# axiom_beta_sensor_cmv12000_tht_v0_16_c4f.net
KiCad netlist of a schematic drawn in EAGLE
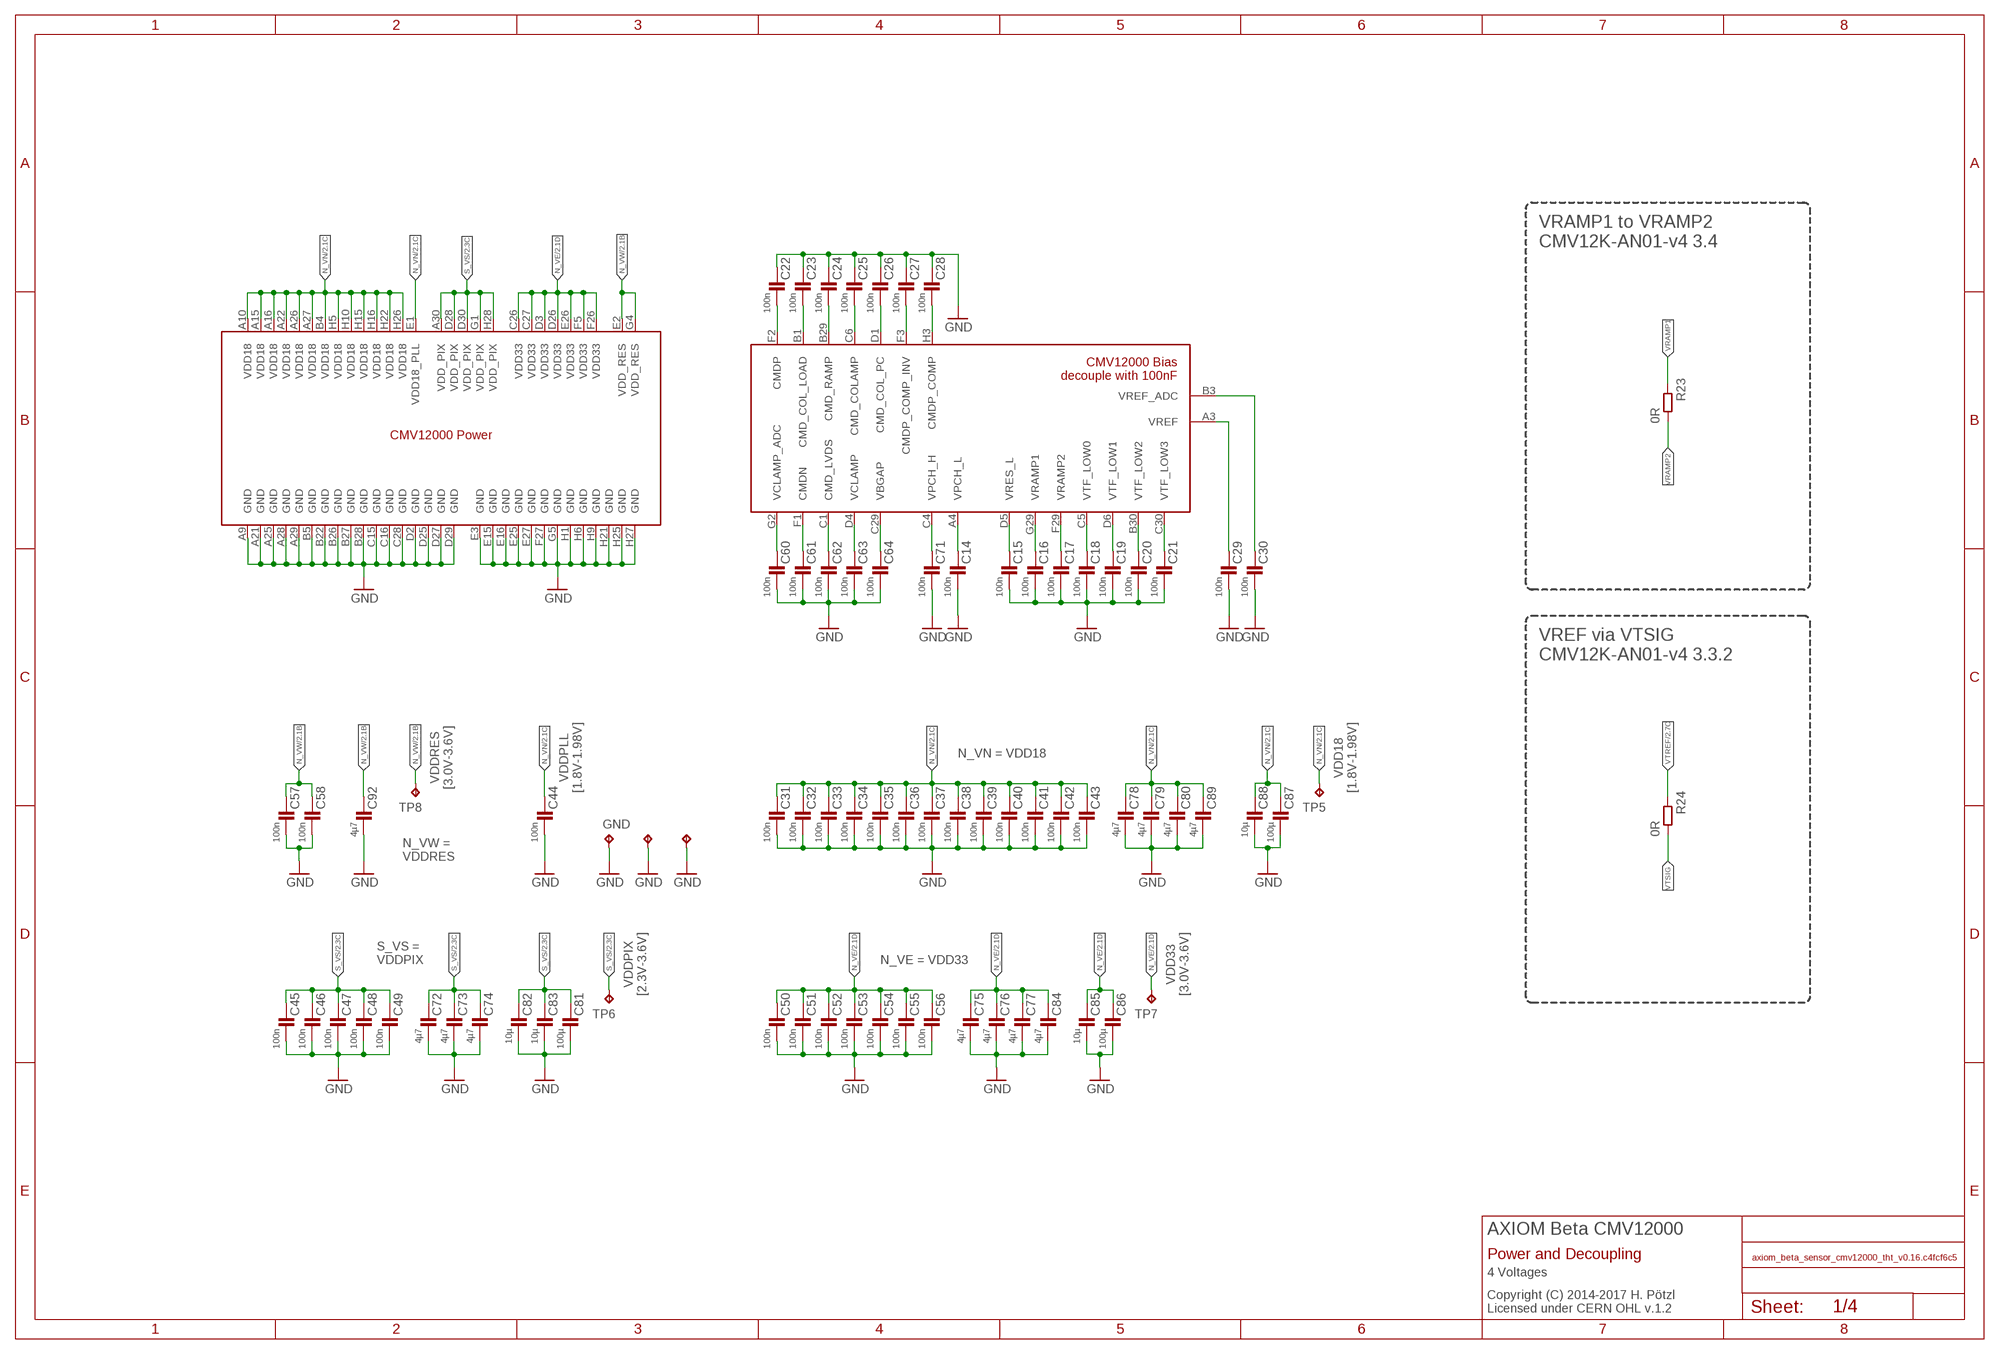
[diagram p0: schematic, sheet 1]
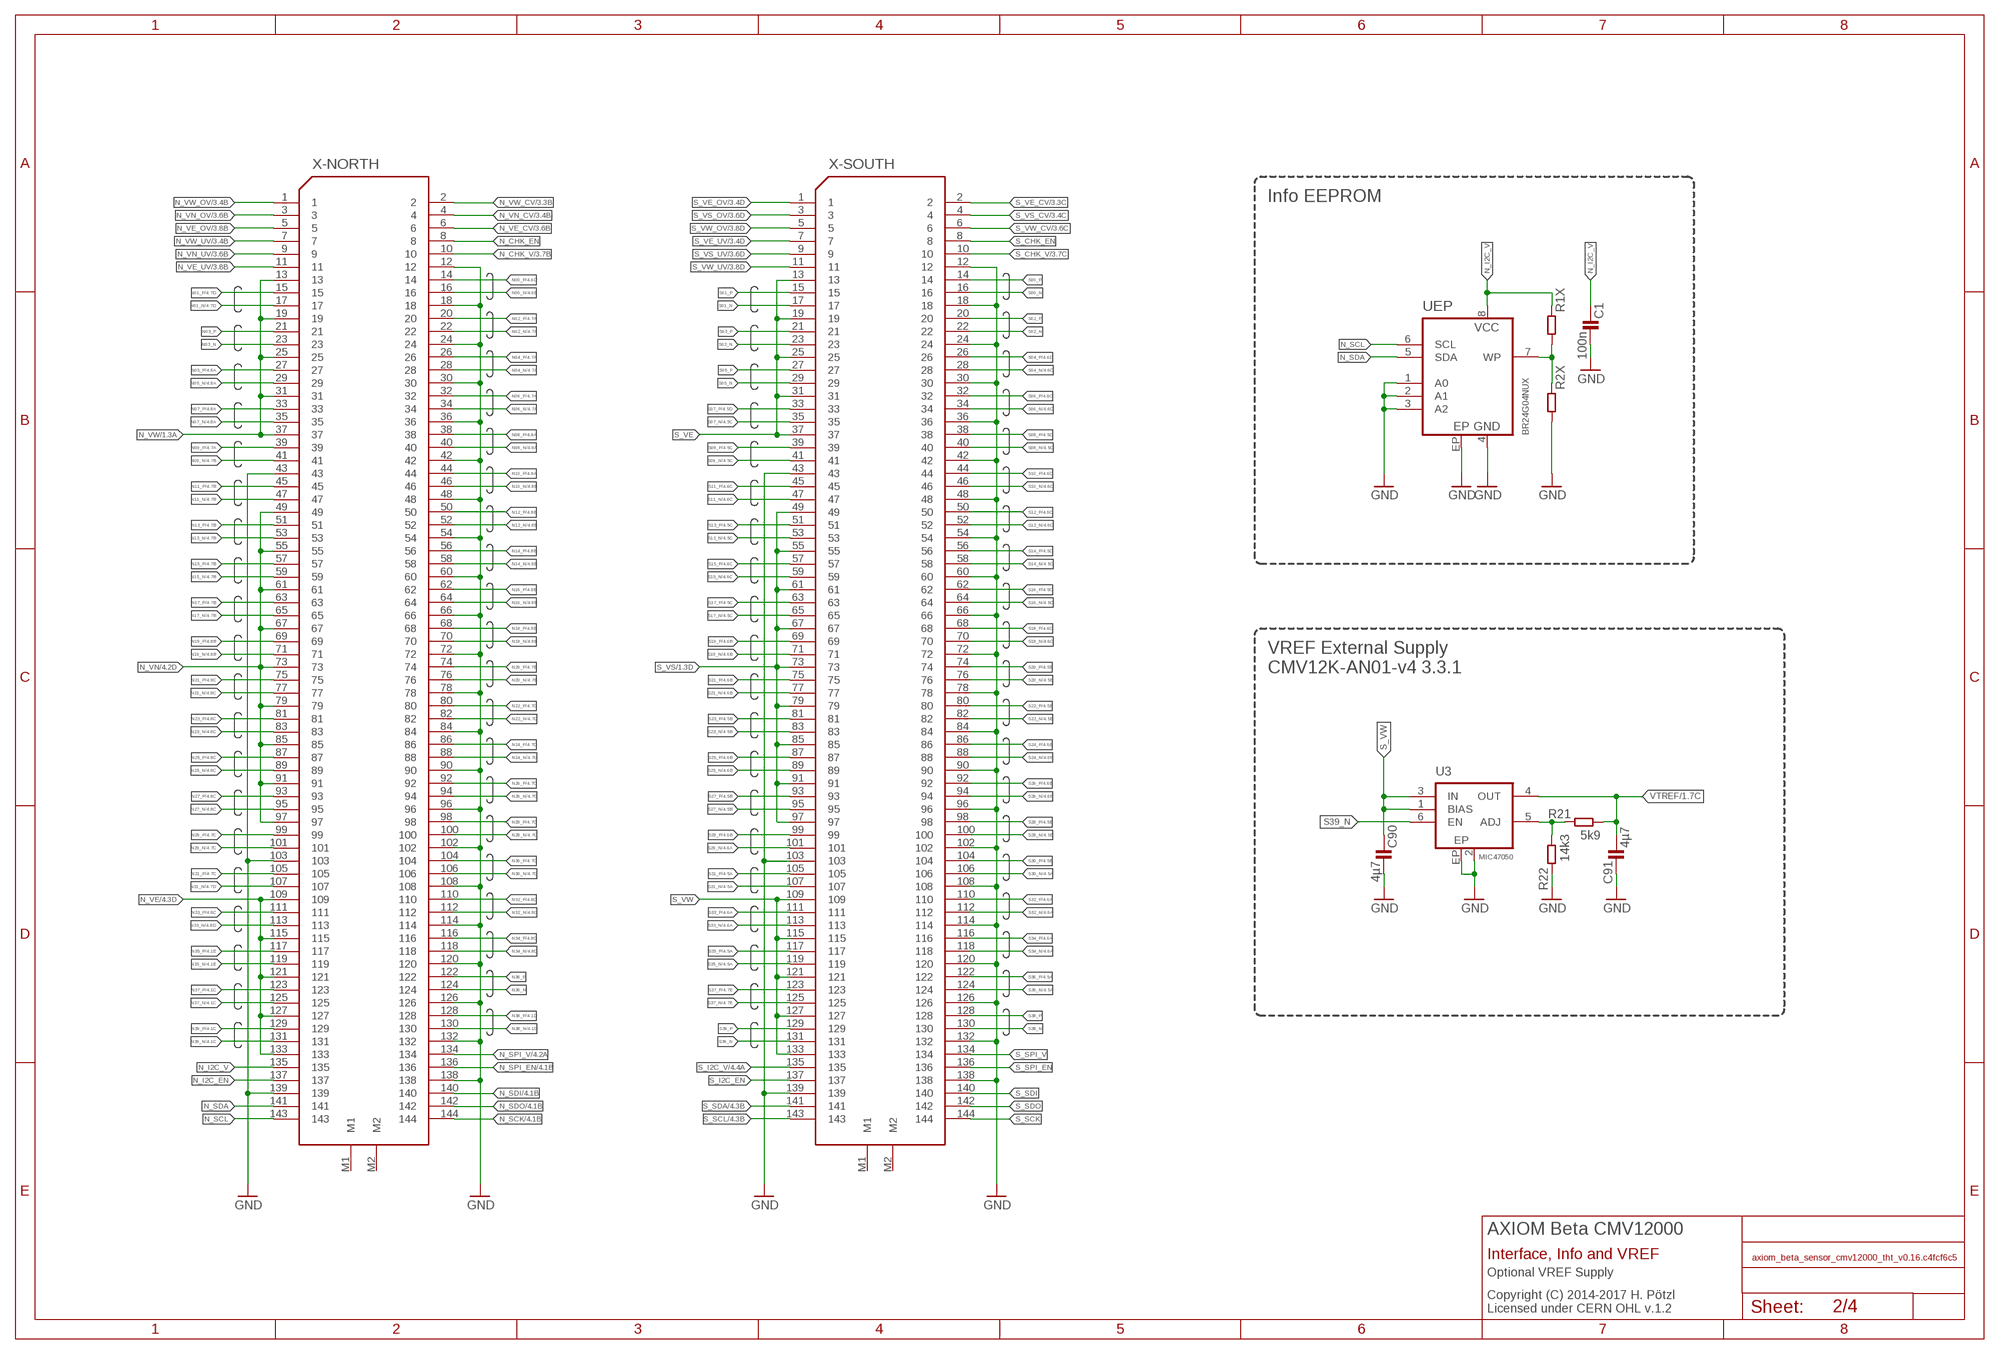
[diagram p1: schematic, sheet 2]
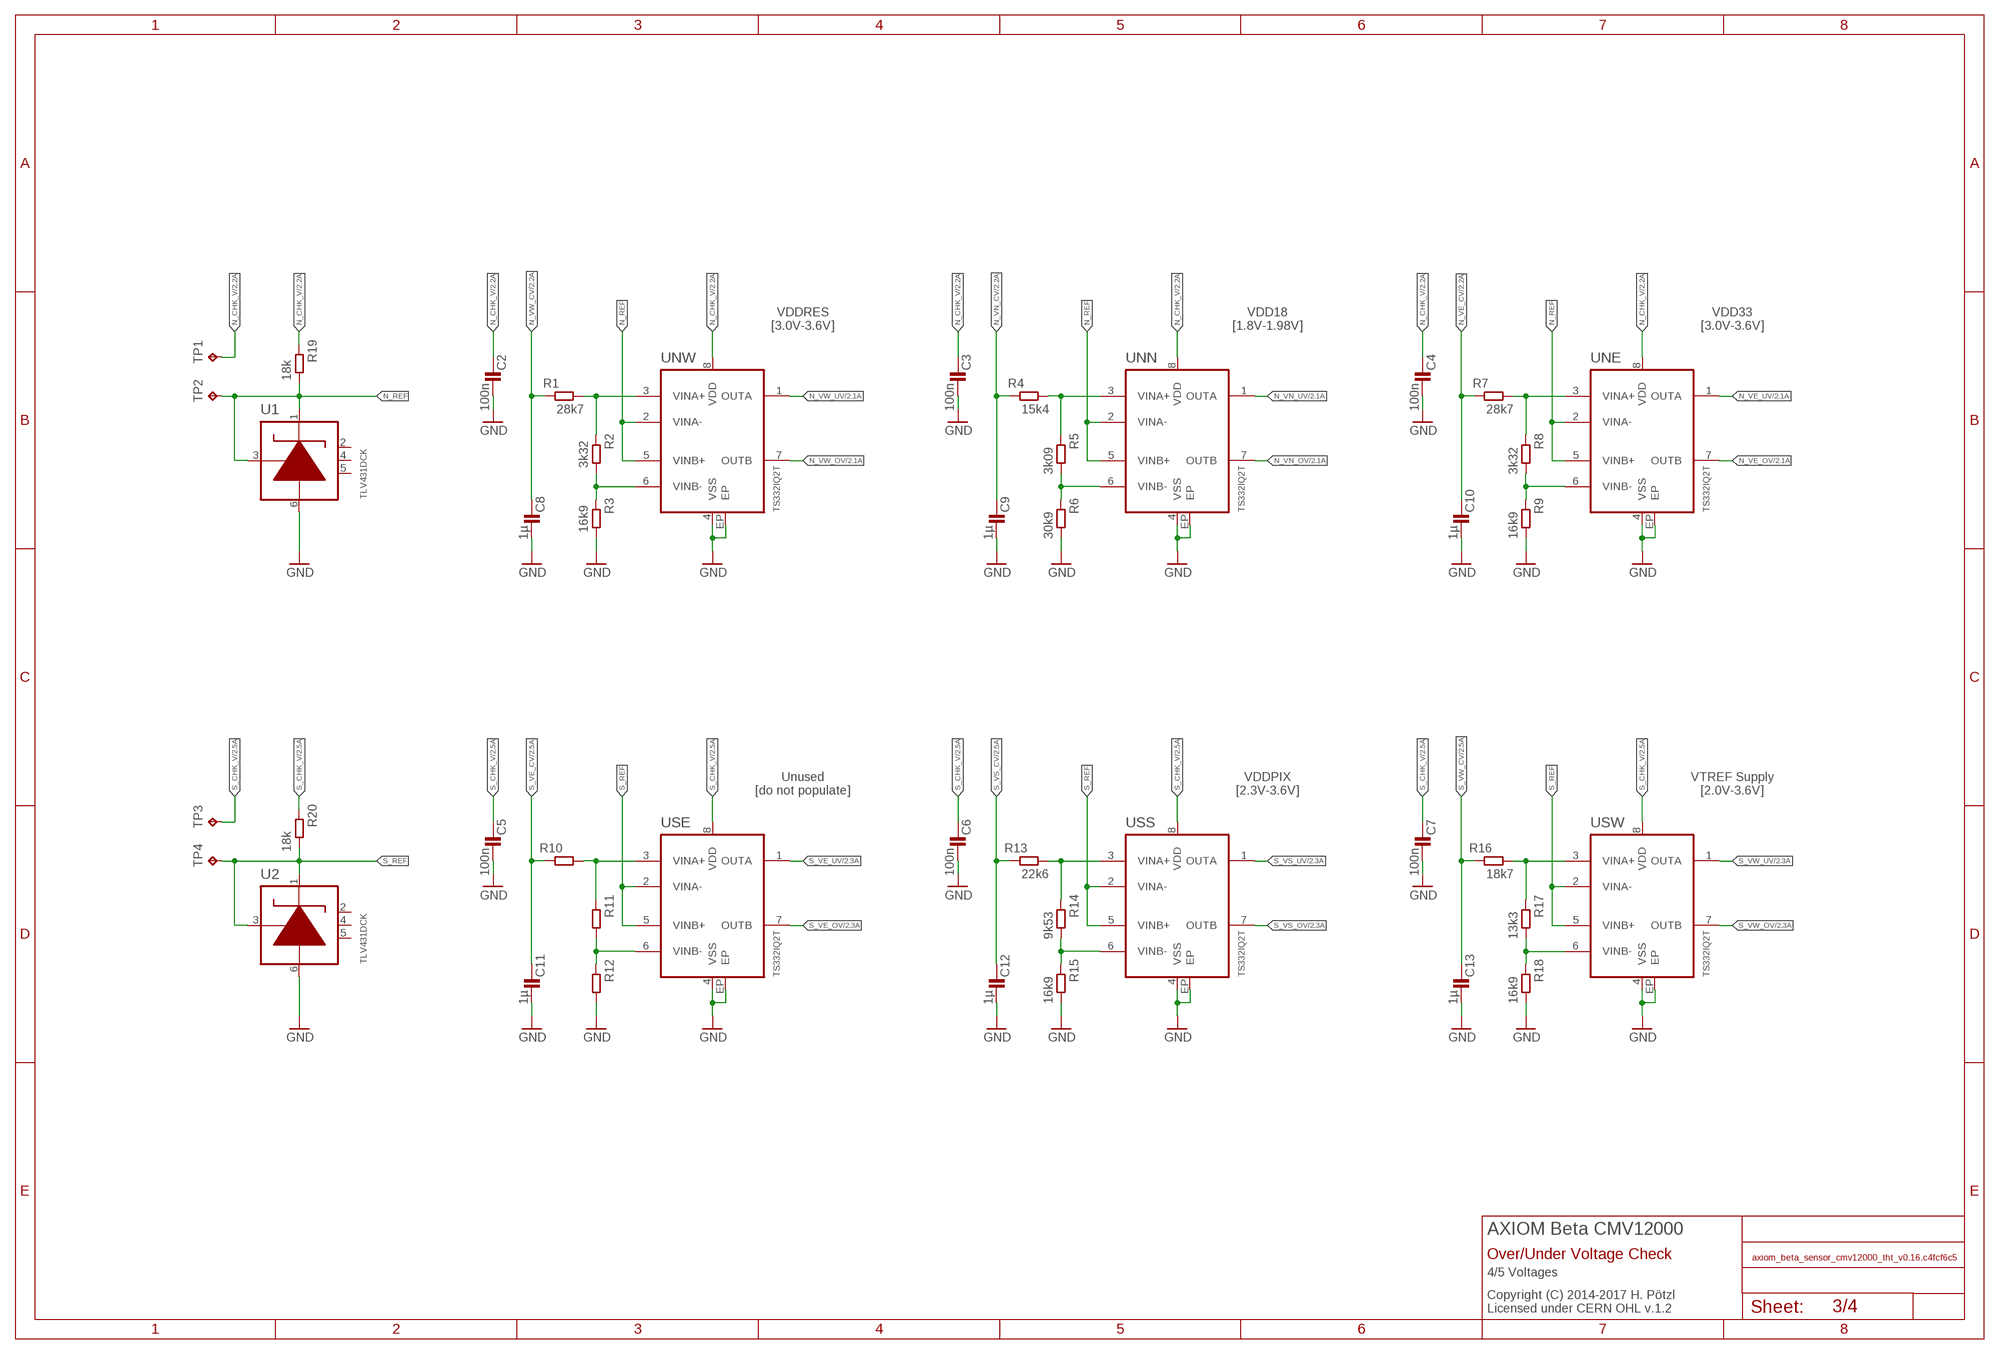
[diagram p2: schematic, sheet 3]
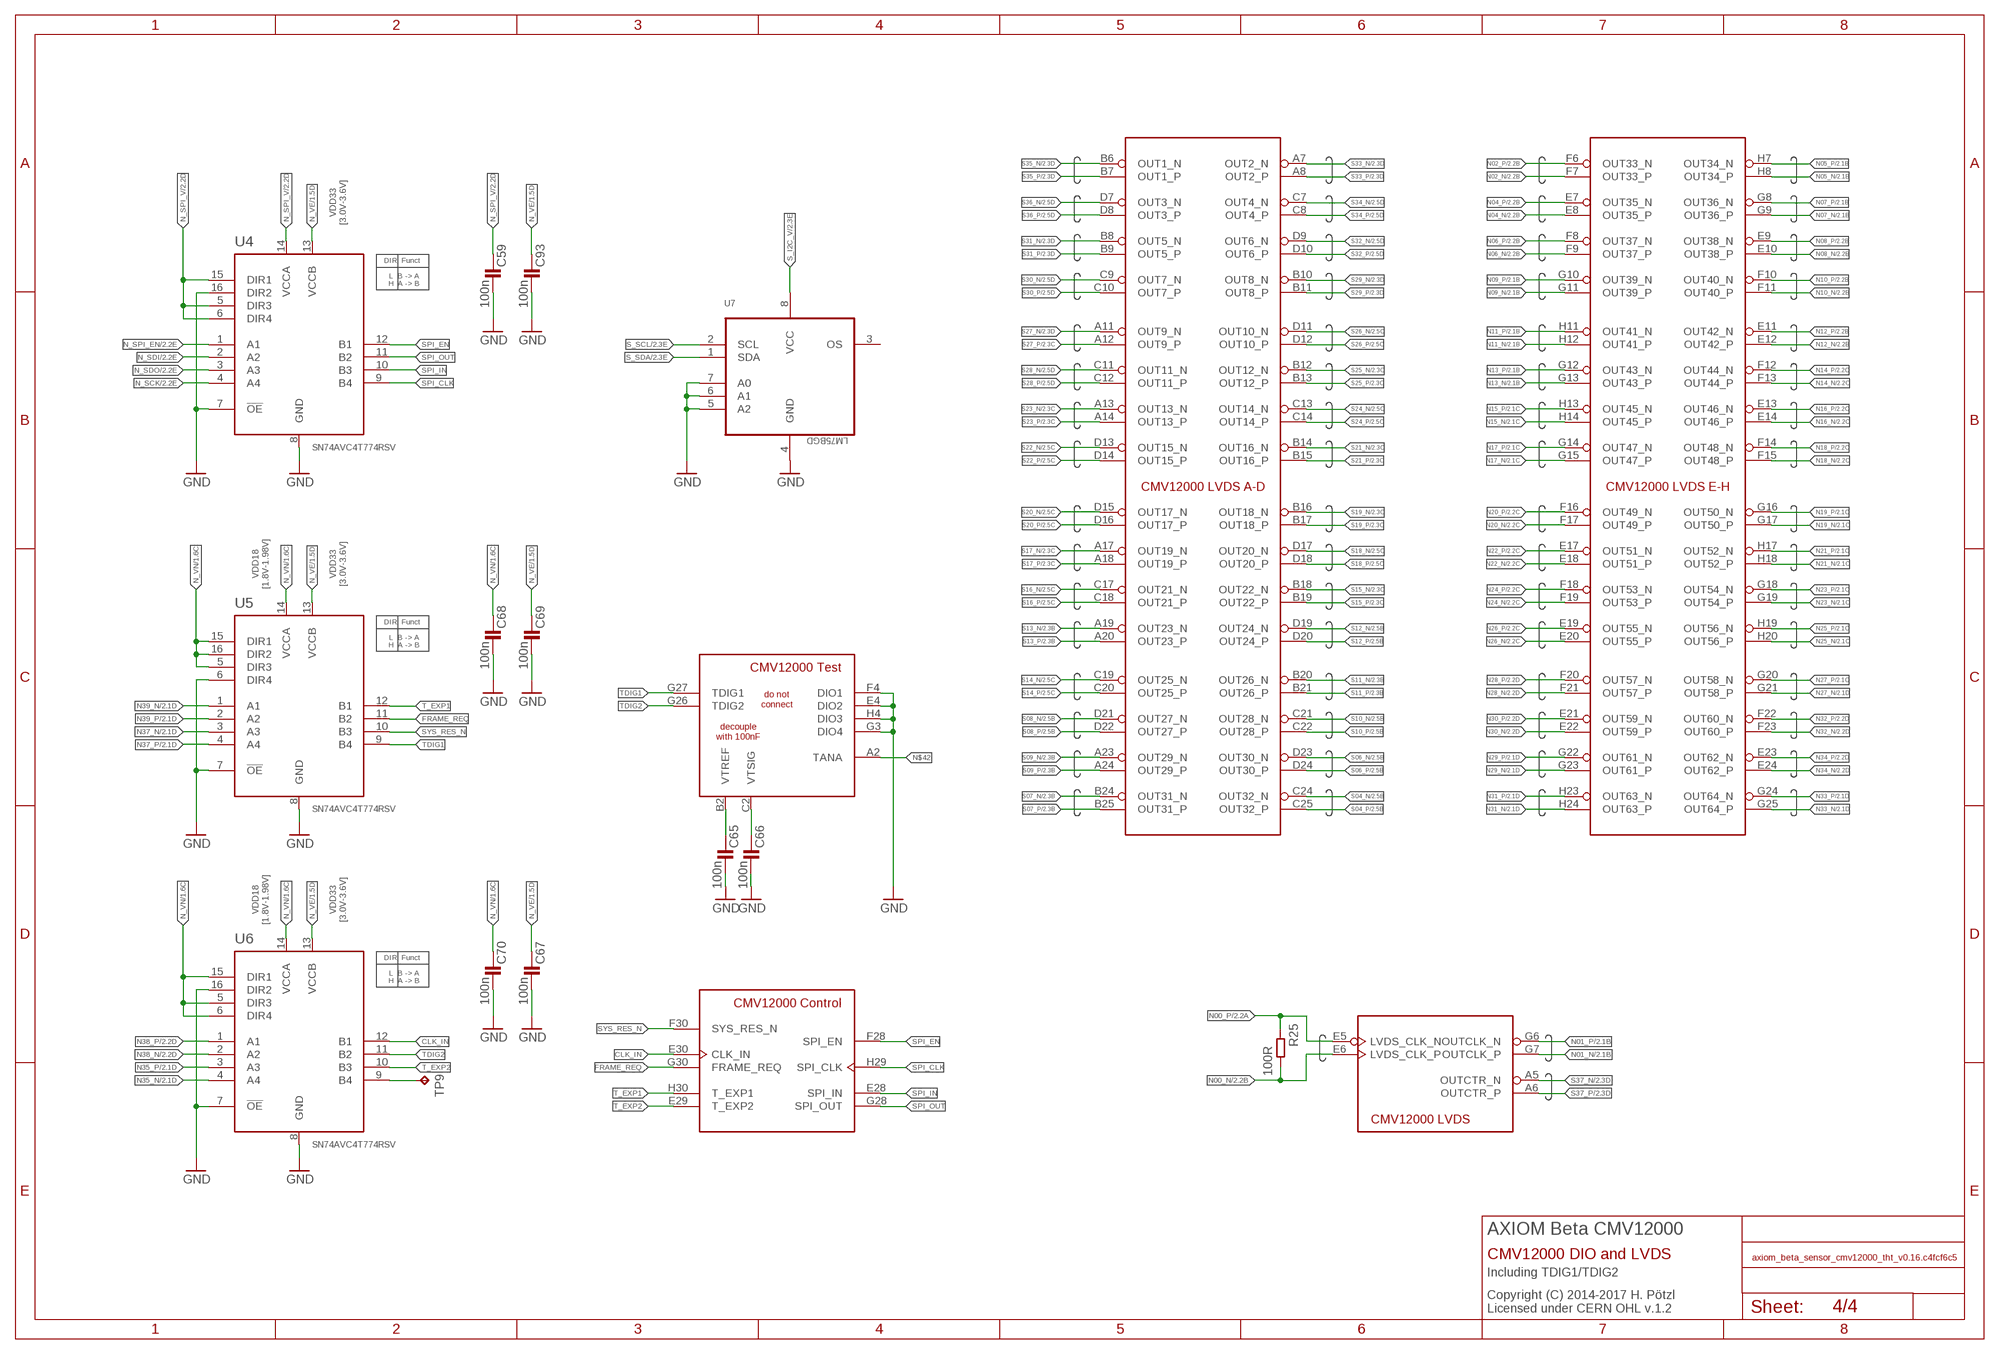
[diagram p3: schematic, sheet 4]

(export (version "E")
  (design (tool "Eeschema 10.0.6"))
  (components
    (comp (ref "C2")
      (value "100n")
      (footprint "eagle-import:0402-C")
      (libsource (lib "eagle-import") (part "C0402-C"))
    )
    (comp (ref "C3")
      (value "100n")
      (footprint "eagle-import:0402-C")
      (libsource (lib "eagle-import") (part "C0402-C"))
    )
    (comp (ref "C4")
      (value "100n")
      (footprint "eagle-import:0402-C")
      (libsource (lib "eagle-import") (part "C0402-C"))
    )
    (comp (ref "C5")
      (value "100n")
      (footprint "eagle-import:0402-C")
      (libsource (lib "eagle-import") (part "C0402-C"))
    )
    (comp (ref "C6")
      (value "100n")
      (footprint "eagle-import:0402-C")
      (libsource (lib "eagle-import") (part "C0402-C"))
    )
    (comp (ref "C7")
      (value "100n")
      (footprint "eagle-import:0402-C")
      (libsource (lib "eagle-import") (part "C0402-C"))
    )
    (comp (ref "C8")
      (value "1µ")
      (footprint "eagle-import:0402-C")
      (libsource (lib "eagle-import") (part "C0402-C"))
    )
    (comp (ref "C9")
      (value "1µ")
      (footprint "eagle-import:0402-C")
      (libsource (lib "eagle-import") (part "C0402-C"))
    )
    (comp (ref "C10")
      (value "1µ")
      (footprint "eagle-import:0402-C")
      (libsource (lib "eagle-import") (part "C0402-C"))
    )
    (comp (ref "C11")
      (value "1µ")
      (footprint "eagle-import:0402-C")
      (libsource (lib "eagle-import") (part "C0402-C"))
    )
    (comp (ref "C12")
      (value "1µ")
      (footprint "eagle-import:0402-C")
      (libsource (lib "eagle-import") (part "C0402-C"))
    )
    (comp (ref "C13")
      (value "1µ")
      (footprint "eagle-import:0402-C")
      (libsource (lib "eagle-import") (part "C0402-C"))
    )
    (comp (ref "R1")
      (value "28k7")
      (footprint "eagle-import:0402-C")
      (libsource (lib "eagle-import") (part "R0402-C"))
    )
    (comp (ref "R2")
      (value "3k32")
      (footprint "eagle-import:0402-C")
      (libsource (lib "eagle-import") (part "R0402-C"))
    )
    (comp (ref "R3")
      (value "16k9")
      (footprint "eagle-import:0402-C")
      (libsource (lib "eagle-import") (part "R0402-C"))
    )
    (comp (ref "R4")
      (value "15k4")
      (footprint "eagle-import:0402-C")
      (libsource (lib "eagle-import") (part "R0402-C"))
    )
    (comp (ref "R5")
      (value "3k09")
      (footprint "eagle-import:0402-C")
      (libsource (lib "eagle-import") (part "R0402-C"))
    )
    (comp (ref "R6")
      (value "30k9")
      (footprint "eagle-import:0402-C")
      (libsource (lib "eagle-import") (part "R0402-C"))
    )
    (comp (ref "R7")
      (value "28k7")
      (footprint "eagle-import:0402-C")
      (libsource (lib "eagle-import") (part "R0402-C"))
    )
    (comp (ref "R8")
      (value "3k32")
      (footprint "eagle-import:0402-C")
      (libsource (lib "eagle-import") (part "R0402-C"))
    )
    (comp (ref "R9")
      (value "16k9")
      (footprint "eagle-import:0402-C")
      (libsource (lib "eagle-import") (part "R0402-C"))
    )
    (comp (ref "R10")
      (value "R0402-C")
      (footprint "eagle-import:0402-C")
      (libsource (lib "eagle-import") (part "R0402-C"))
    )
    (comp (ref "R11")
      (value "R0402-C")
      (footprint "eagle-import:0402-C")
      (libsource (lib "eagle-import") (part "R0402-C"))
    )
    (comp (ref "R12")
      (value "R0402-C")
      (footprint "eagle-import:0402-C")
      (libsource (lib "eagle-import") (part "R0402-C"))
    )
    (comp (ref "R13")
      (value "22k6")
      (footprint "eagle-import:0402-C")
      (libsource (lib "eagle-import") (part "R0402-C"))
    )
    (comp (ref "R14")
      (value "9k53")
      (footprint "eagle-import:0402-C")
      (libsource (lib "eagle-import") (part "R0402-C"))
    )
    (comp (ref "R15")
      (value "16k9")
      (footprint "eagle-import:0402-C")
      (libsource (lib "eagle-import") (part "R0402-C"))
    )
    (comp (ref "R16")
      (value "18k7")
      (footprint "eagle-import:0402-C")
      (libsource (lib "eagle-import") (part "R0402-C"))
    )
    (comp (ref "R17")
      (value "13k3")
      (footprint "eagle-import:0402-C")
      (libsource (lib "eagle-import") (part "R0402-C"))
    )
    (comp (ref "R18")
      (value "16k9")
      (footprint "eagle-import:0402-C")
      (libsource (lib "eagle-import") (part "R0402-C"))
    )
    (comp (ref "R19")
      (value "18k")
      (footprint "eagle-import:0402-C")
      (libsource (lib "eagle-import") (part "R0402-C"))
    )
    (comp (ref "R20")
      (value "18k")
      (footprint "eagle-import:0402-C")
      (libsource (lib "eagle-import") (part "R0402-C"))
    )
    (comp (ref "TP1")
      (value "TPTP10R")
      (footprint "eagle-import:TP10R")
      (libsource (lib "eagle-import") (part "TPTP10R"))
    )
    (comp (ref "TP2")
      (value "TPTP10R")
      (footprint "eagle-import:TP10R")
      (libsource (lib "eagle-import") (part "TPTP10R"))
    )
    (comp (ref "TP3")
      (value "TPTP10R")
      (footprint "eagle-import:TP10R")
      (libsource (lib "eagle-import") (part "TPTP10R"))
    )
    (comp (ref "TP4")
      (value "TPTP10R")
      (footprint "eagle-import:TP10R")
      (libsource (lib "eagle-import") (part "TPTP10R"))
    )
    (comp (ref "U1")
      (value "TLV431DCK")
      (footprint "eagle-import:SOT65P210X110-6N")
      (libsource (lib "eagle-import") (part "TLV431DCK"))
    )
    (comp (ref "U2")
      (value "TLV431DCK")
      (footprint "eagle-import:SOT65P210X110-6N")
      (libsource (lib "eagle-import") (part "TLV431DCK"))
    )
    (comp (ref "UNE")
      (value "TS332IQ2T")
      (footprint "eagle-import:DFN200X200X100-9N")
      (libsource (lib "eagle-import") (part "TS332IQ2T"))
    )
    (comp (ref "UNN")
      (value "TS332IQ2T")
      (footprint "eagle-import:DFN200X200X100-9N")
      (libsource (lib "eagle-import") (part "TS332IQ2T"))
    )
    (comp (ref "UNW")
      (value "TS332IQ2T")
      (footprint "eagle-import:DFN200X200X100-9N")
      (libsource (lib "eagle-import") (part "TS332IQ2T"))
    )
    (comp (ref "USE")
      (value "TS332IQ2T")
      (footprint "eagle-import:DFN200X200X100-9N")
      (libsource (lib "eagle-import") (part "TS332IQ2T"))
    )
    (comp (ref "USS")
      (value "TS332IQ2T")
      (footprint "eagle-import:DFN200X200X100-9N")
      (libsource (lib "eagle-import") (part "TS332IQ2T"))
    )
    (comp (ref "USW")
      (value "TS332IQ2T")
      (footprint "eagle-import:DFN200X200X100-9N")
      (libsource (lib "eagle-import") (part "TS332IQ2T"))
    )
    (comp (ref "C59")
      (value "100n")
      (footprint "eagle-import:0402-C")
      (libsource (lib "eagle-import") (part "C0402-C"))
    )
    (comp (ref "C65")
      (value "100n")
      (footprint "eagle-import:0402-C")
      (libsource (lib "eagle-import") (part "C0402-C"))
    )
    (comp (ref "C66")
      (value "100n")
      (footprint "eagle-import:0402-C")
      (libsource (lib "eagle-import") (part "C0402-C"))
    )
    (comp (ref "C67")
      (value "100n")
      (footprint "eagle-import:0402-C")
      (libsource (lib "eagle-import") (part "C0402-C"))
    )
    (comp (ref "C68")
      (value "100n")
      (footprint "eagle-import:0402-C")
      (libsource (lib "eagle-import") (part "C0402-C"))
    )
    (comp (ref "C69")
      (value "100n")
      (footprint "eagle-import:0402-C")
      (libsource (lib "eagle-import") (part "C0402-C"))
    )
    (comp (ref "C70")
      (value "100n")
      (footprint "eagle-import:0402-C")
      (libsource (lib "eagle-import") (part "C0402-C"))
    )
    (comp (ref "C93")
      (value "100n")
      (footprint "eagle-import:0402-C")
      (libsource (lib "eagle-import") (part "C0402-C"))
    )
    (comp (ref "R25")
      (value "100R")
      (footprint "eagle-import:0402-C")
      (libsource (lib "eagle-import") (part "R0402-C"))
    )
    (comp (ref "SENSOR")
      (value "CMV12000ANDON-CREAM")
      (footprint "eagle-import:10-30-07-237-400T4-CREAM")
      (libsource (lib "eagle-import") (part "CMV12000ANDON-CREAM"))
    )
    (comp (ref "TP9")
      (value "TPTP10R")
      (footprint "eagle-import:TP10R")
      (libsource (lib "eagle-import") (part "TPTP10R"))
    )
    (comp (ref "U4")
      (value "SN74AVC4T774RSV")
      (footprint "eagle-import:QFN40P185X265X55-16N")
      (libsource (lib "eagle-import") (part "SN74AVC4T774RSV"))
    )
    (comp (ref "U5")
      (value "SN74AVC4T774RSV")
      (footprint "eagle-import:QFN40P185X265X55-16N")
      (libsource (lib "eagle-import") (part "SN74AVC4T774RSV"))
    )
    (comp (ref "U6")
      (value "SN74AVC4T774RSV")
      (footprint "eagle-import:QFN40P185X265X55-16N")
      (libsource (lib "eagle-import") (part "SN74AVC4T774RSV"))
    )
    (comp (ref "U7")
      (value "LM75BGD")
      (footprint "eagle-import:SOT996-2_3")
      (libsource (lib "eagle-import") (part "LM75BGD"))
    )
    (comp (ref "C1")
      (value "100n")
      (footprint "eagle-import:0402-C")
      (libsource (lib "eagle-import") (part "C0402-C"))
    )
    (comp (ref "C90")
      (value "4µ7")
      (footprint "eagle-import:0402-C")
      (libsource (lib "eagle-import") (part "C0402-C"))
    )
    (comp (ref "C91")
      (value "4µ7")
      (footprint "eagle-import:0402-C")
      (libsource (lib "eagle-import") (part "C0402-C"))
    )
    (comp (ref "R1X")
      (value "R0402-C")
      (footprint "eagle-import:0402-C")
      (libsource (lib "eagle-import") (part "R0402-C"))
    )
    (comp (ref "R2X")
      (value "R0402-C")
      (footprint "eagle-import:0402-C")
      (libsource (lib "eagle-import") (part "R0402-C"))
    )
    (comp (ref "R21")
      (value "5k9")
      (footprint "eagle-import:0402-C")
      (libsource (lib "eagle-import") (part "R0402-C"))
    )
    (comp (ref "R22")
      (value "14k3")
      (footprint "eagle-import:0402-C")
      (libsource (lib "eagle-import") (part "R0402-C"))
    )
    (comp (ref "U3")
      (value "MIC47050")
      (footprint "eagle-import:MLF-6")
      (libsource (lib "eagle-import") (part "MIC47050-ADJ"))
    )
    (comp (ref "UEP")
      (value "BR24G04NUX")
      (footprint "eagle-import:DFN200X300X100-9N")
      (libsource (lib "eagle-import") (part "BR24G04NUX"))
    )
    (comp (ref "X-NORTH")
      (value "FX10-144P")
      (footprint "eagle-import:FX10A-144P")
      (libsource (lib "eagle-import") (part "FX10-144P"))
    )
    (comp (ref "X-SOUTH")
      (value "FX10-144P")
      (footprint "eagle-import:FX10A-144P")
      (libsource (lib "eagle-import") (part "FX10-144P"))
    )
    (comp (ref "C14")
      (value "100n")
      (footprint "eagle-import:0402-C")
      (libsource (lib "eagle-import") (part "C0402-C"))
    )
    (comp (ref "C15")
      (value "100n")
      (footprint "eagle-import:0402-C")
      (libsource (lib "eagle-import") (part "C0402-C"))
    )
    (comp (ref "C16")
      (value "100n")
      (footprint "eagle-import:0402-C")
      (libsource (lib "eagle-import") (part "C0402-C"))
    )
    (comp (ref "C17")
      (value "100n")
      (footprint "eagle-import:0402-C")
      (libsource (lib "eagle-import") (part "C0402-C"))
    )
    (comp (ref "C18")
      (value "100n")
      (footprint "eagle-import:0402-C")
      (libsource (lib "eagle-import") (part "C0402-C"))
    )
    (comp (ref "C19")
      (value "100n")
      (footprint "eagle-import:0402-C")
      (libsource (lib "eagle-import") (part "C0402-C"))
    )
    (comp (ref "C20")
      (value "100n")
      (footprint "eagle-import:0402-C")
      (libsource (lib "eagle-import") (part "C0402-C"))
    )
    (comp (ref "C21")
      (value "100n")
      (footprint "eagle-import:0402-C")
      (libsource (lib "eagle-import") (part "C0402-C"))
    )
    (comp (ref "C22")
      (value "100n")
      (footprint "eagle-import:0402-C")
      (libsource (lib "eagle-import") (part "C0402-C"))
    )
    (comp (ref "C23")
      (value "100n")
      (footprint "eagle-import:0402-C")
      (libsource (lib "eagle-import") (part "C0402-C"))
    )
    (comp (ref "C24")
      (value "100n")
      (footprint "eagle-import:0402-C")
      (libsource (lib "eagle-import") (part "C0402-C"))
    )
    (comp (ref "C25")
      (value "100n")
      (footprint "eagle-import:0402-C")
      (libsource (lib "eagle-import") (part "C0402-C"))
    )
    (comp (ref "C26")
      (value "100n")
      (footprint "eagle-import:0402-C")
      (libsource (lib "eagle-import") (part "C0402-C"))
    )
    (comp (ref "C27")
      (value "100n")
      (footprint "eagle-import:0402-C")
      (libsource (lib "eagle-import") (part "C0402-C"))
    )
    (comp (ref "C28")
      (value "100n")
      (footprint "eagle-import:0402-C")
      (libsource (lib "eagle-import") (part "C0402-C"))
    )
    (comp (ref "C29")
      (value "100n")
      (footprint "eagle-import:0402-C")
      (libsource (lib "eagle-import") (part "C0402-C"))
    )
    (comp (ref "C30")
      (value "100n")
      (footprint "eagle-import:0402-C")
      (libsource (lib "eagle-import") (part "C0402-C"))
    )
    (comp (ref "C31")
      (value "100n")
      (footprint "eagle-import:0402-C")
      (libsource (lib "eagle-import") (part "C0402-C"))
    )
    (comp (ref "C32")
      (value "100n")
      (footprint "eagle-import:0402-C")
      (libsource (lib "eagle-import") (part "C0402-C"))
    )
    (comp (ref "C33")
      (value "100n")
      (footprint "eagle-import:0402-C")
      (libsource (lib "eagle-import") (part "C0402-C"))
    )
    (comp (ref "C34")
      (value "100n")
      (footprint "eagle-import:0402-C")
      (libsource (lib "eagle-import") (part "C0402-C"))
    )
    (comp (ref "C35")
      (value "100n")
      (footprint "eagle-import:0402-C")
      (libsource (lib "eagle-import") (part "C0402-C"))
    )
    (comp (ref "C36")
      (value "100n")
      (footprint "eagle-import:0402-C")
      (libsource (lib "eagle-import") (part "C0402-C"))
    )
    (comp (ref "C37")
      (value "100n")
      (footprint "eagle-import:0402-C")
      (libsource (lib "eagle-import") (part "C0402-C"))
    )
    (comp (ref "C38")
      (value "100n")
      (footprint "eagle-import:0402-C")
      (libsource (lib "eagle-import") (part "C0402-C"))
    )
    (comp (ref "C39")
      (value "100n")
      (footprint "eagle-import:0402-C")
      (libsource (lib "eagle-import") (part "C0402-C"))
    )
    (comp (ref "C40")
      (value "100n")
      (footprint "eagle-import:0402-C")
      (libsource (lib "eagle-import") (part "C0402-C"))
    )
    (comp (ref "C41")
      (value "100n")
      (footprint "eagle-import:0402-C")
      (libsource (lib "eagle-import") (part "C0402-C"))
    )
    (comp (ref "C42")
      (value "100n")
      (footprint "eagle-import:0402-C")
      (libsource (lib "eagle-import") (part "C0402-C"))
    )
    (comp (ref "C43")
      (value "100n")
      (footprint "eagle-import:0402-C")
      (libsource (lib "eagle-import") (part "C0402-C"))
    )
    (comp (ref "C44")
      (value "100n")
      (footprint "eagle-import:0402-C")
      (libsource (lib "eagle-import") (part "C0402-C"))
    )
    (comp (ref "C45")
      (value "100n")
      (footprint "eagle-import:0402-C")
      (libsource (lib "eagle-import") (part "C0402-C"))
    )
    (comp (ref "C46")
      (value "100n")
      (footprint "eagle-import:0402-C")
      (libsource (lib "eagle-import") (part "C0402-C"))
    )
    (comp (ref "C47")
      (value "100n")
      (footprint "eagle-import:0402-C")
      (libsource (lib "eagle-import") (part "C0402-C"))
    )
    (comp (ref "C48")
      (value "100n")
      (footprint "eagle-import:0402-C")
      (libsource (lib "eagle-import") (part "C0402-C"))
    )
    (comp (ref "C49")
      (value "100n")
      (footprint "eagle-import:0402-C")
      (libsource (lib "eagle-import") (part "C0402-C"))
    )
    (comp (ref "C50")
      (value "100n")
      (footprint "eagle-import:0402-C")
      (libsource (lib "eagle-import") (part "C0402-C"))
    )
    (comp (ref "C51")
      (value "100n")
      (footprint "eagle-import:0402-C")
      (libsource (lib "eagle-import") (part "C0402-C"))
    )
    (comp (ref "C52")
      (value "100n")
      (footprint "eagle-import:0402-C")
      (libsource (lib "eagle-import") (part "C0402-C"))
    )
    (comp (ref "C53")
      (value "100n")
      (footprint "eagle-import:0402-C")
      (libsource (lib "eagle-import") (part "C0402-C"))
    )
    (comp (ref "C54")
      (value "100n")
      (footprint "eagle-import:0402-C")
      (libsource (lib "eagle-import") (part "C0402-C"))
    )
    (comp (ref "C55")
      (value "100n")
      (footprint "eagle-import:0402-C")
      (libsource (lib "eagle-import") (part "C0402-C"))
    )
    (comp (ref "C56")
      (value "100n")
      (footprint "eagle-import:0402-C")
      (libsource (lib "eagle-import") (part "C0402-C"))
    )
    (comp (ref "C57")
      (value "100n")
      (footprint "eagle-import:0402-C")
      (libsource (lib "eagle-import") (part "C0402-C"))
    )
    (comp (ref "C58")
      (value "100n")
      (footprint "eagle-import:0402-C")
      (libsource (lib "eagle-import") (part "C0402-C"))
    )
    (comp (ref "C60")
      (value "100n")
      (footprint "eagle-import:0402-C")
      (libsource (lib "eagle-import") (part "C0402-C"))
    )
    (comp (ref "C61")
      (value "100n")
      (footprint "eagle-import:0402-C")
      (libsource (lib "eagle-import") (part "C0402-C"))
    )
    (comp (ref "C62")
      (value "100n")
      (footprint "eagle-import:0402-C")
      (libsource (lib "eagle-import") (part "C0402-C"))
    )
    (comp (ref "C63")
      (value "100n")
      (footprint "eagle-import:0402-C")
      (libsource (lib "eagle-import") (part "C0402-C"))
    )
    (comp (ref "C64")
      (value "100n")
      (footprint "eagle-import:0402-C")
      (libsource (lib "eagle-import") (part "C0402-C"))
    )
    (comp (ref "C71")
      (value "100n")
      (footprint "eagle-import:0402-C")
      (libsource (lib "eagle-import") (part "C0402-C"))
    )
    (comp (ref "C72")
      (value "4µ7")
      (footprint "eagle-import:0402-B")
      (libsource (lib "eagle-import") (part "C0402-B"))
    )
    (comp (ref "C73")
      (value "4µ7")
      (footprint "eagle-import:0402-C")
      (libsource (lib "eagle-import") (part "C0402-C"))
    )
    (comp (ref "C74")
      (value "4µ7")
      (footprint "eagle-import:0402-C")
      (libsource (lib "eagle-import") (part "C0402-C"))
    )
    (comp (ref "C75")
      (value "4µ7")
      (footprint "eagle-import:0402-C")
      (libsource (lib "eagle-import") (part "C0402-C"))
    )
    (comp (ref "C76")
      (value "4µ7")
      (footprint "eagle-import:0402-C")
      (libsource (lib "eagle-import") (part "C0402-C"))
    )
    (comp (ref "C77")
      (value "4µ7")
      (footprint "eagle-import:0402-B")
      (libsource (lib "eagle-import") (part "C0402-B"))
    )
    (comp (ref "C78")
      (value "4µ7")
      (footprint "eagle-import:0402-B")
      (libsource (lib "eagle-import") (part "C0402-B"))
    )
    (comp (ref "C79")
      (value "4µ7")
      (footprint "eagle-import:0402-C")
      (libsource (lib "eagle-import") (part "C0402-C"))
    )
    (comp (ref "C80")
      (value "4µ7")
      (footprint "eagle-import:0402-C")
      (libsource (lib "eagle-import") (part "C0402-C"))
    )
    (comp (ref "C81")
      (value "100µ")
      (footprint "eagle-import:1206-B")
      (libsource (lib "eagle-import") (part "C1206-B"))
    )
    (comp (ref "C82")
      (value "10µ")
      (footprint "eagle-import:0603-C")
      (libsource (lib "eagle-import") (part "C0603-C"))
    )
    (comp (ref "C83")
      (value "10µ")
      (footprint "eagle-import:0603-C")
      (libsource (lib "eagle-import") (part "C0603-C"))
    )
    (comp (ref "C84")
      (value "4µ7")
      (footprint "eagle-import:0402-C")
      (libsource (lib "eagle-import") (part "C0402-C"))
    )
    (comp (ref "C85")
      (value "10µ")
      (footprint "eagle-import:0603-C")
      (libsource (lib "eagle-import") (part "C0603-C"))
    )
    (comp (ref "C86")
      (value "100µ")
      (footprint "eagle-import:1206-B")
      (libsource (lib "eagle-import") (part "C1206-B"))
    )
    (comp (ref "C87")
      (value "100µ")
      (footprint "eagle-import:1206-B")
      (libsource (lib "eagle-import") (part "C1206-B"))
    )
    (comp (ref "C88")
      (value "10µ")
      (footprint "eagle-import:0603-C")
      (libsource (lib "eagle-import") (part "C0603-C"))
    )
    (comp (ref "C89")
      (value "4µ7")
      (footprint "eagle-import:0402-C")
      (libsource (lib "eagle-import") (part "C0402-C"))
    )
    (comp (ref "C92")
      (value "4µ7")
      (footprint "eagle-import:0402-C")
      (libsource (lib "eagle-import") (part "C0402-C"))
    )
    (comp (ref "GND")
      (value "TPTP10R")
      (footprint "eagle-import:TP10R")
      (libsource (lib "eagle-import") (part "TPTP10R"))
    )
    (comp (ref "GND75")
      (value "TPTP10R")
      (footprint "eagle-import:TP10R")
      (libsource (lib "eagle-import") (part "TPTP10R"))
    )
    (comp (ref "GND77")
      (value "TPTP10R")
      (footprint "eagle-import:TP10R")
      (libsource (lib "eagle-import") (part "TPTP10R"))
    )
    (comp (ref "R23")
      (value "0R")
      (footprint "eagle-import:0402-C")
      (libsource (lib "eagle-import") (part "R0402-C"))
    )
    (comp (ref "R24")
      (value "0R")
      (footprint "eagle-import:0402-C")
      (libsource (lib "eagle-import") (part "R0402-C"))
    )
    (comp (ref "TP5")
      (value "TPTP10R")
      (footprint "eagle-import:TP10R")
      (libsource (lib "eagle-import") (part "TPTP10R"))
    )
    (comp (ref "TP6")
      (value "TPTP10R")
      (footprint "eagle-import:TP10R")
      (libsource (lib "eagle-import") (part "TPTP10R"))
    )
    (comp (ref "TP7")
      (value "TPTP10R")
      (footprint "eagle-import:TP10R")
      (libsource (lib "eagle-import") (part "TPTP10R"))
    )
    (comp (ref "TP8")
      (value "TPTP10R")
      (footprint "eagle-import:TP10R")
      (libsource (lib "eagle-import") (part "TPTP10R"))
    )
  )
  (nets
    (net (code "1") (name "CLK_IN") (class "Default")
      (node (ref "SENSOR") (pin "E30") (pinfunction "CLK_IN_E30") (pintype "input"))
      (node (ref "U6") (pin "12") (pinfunction "B1_12") (pintype "bidirectional"))
    )
    (net (code "2") (name "FRAME_REQ") (class "Default")
      (node (ref "SENSOR") (pin "G30") (pinfunction "FRAME_REQ_G30") (pintype "input"))
      (node (ref "U5") (pin "11") (pinfunction "B2_11") (pintype "bidirectional"))
    )
    (net (code "3") (name "GND") (class "Default")
      (node (ref "C1") (pin "2") (pinfunction "2_2") (pintype "passive"))
      (node (ref "C10") (pin "2") (pinfunction "2_2") (pintype "passive"))
      (node (ref "C11") (pin "2") (pinfunction "2_2") (pintype "passive"))
      (node (ref "C12") (pin "2") (pinfunction "2_2") (pintype "passive"))
      (node (ref "C13") (pin "2") (pinfunction "2_2") (pintype "passive"))
      (node (ref "C14") (pin "2") (pinfunction "2_2") (pintype "passive"))
      (node (ref "C15") (pin "2") (pinfunction "2_2") (pintype "passive"))
      (node (ref "C16") (pin "2") (pinfunction "2_2") (pintype "passive"))
      (node (ref "C17") (pin "2") (pinfunction "2_2") (pintype "passive"))
      (node (ref "C18") (pin "2") (pinfunction "2_2") (pintype "passive"))
      (node (ref "C19") (pin "2") (pinfunction "2_2") (pintype "passive"))
      (node (ref "C2") (pin "2") (pinfunction "2_2") (pintype "passive"))
      (node (ref "C20") (pin "2") (pinfunction "2_2") (pintype "passive"))
      (node (ref "C21") (pin "2") (pinfunction "2_2") (pintype "passive"))
      (node (ref "C22") (pin "1") (pinfunction "1_1") (pintype "passive"))
      (node (ref "C23") (pin "1") (pinfunction "1_1") (pintype "passive"))
      (node (ref "C24") (pin "1") (pinfunction "1_1") (pintype "passive"))
      (node (ref "C25") (pin "1") (pinfunction "1_1") (pintype "passive"))
      (node (ref "C26") (pin "1") (pinfunction "1_1") (pintype "passive"))
      (node (ref "C27") (pin "1") (pinfunction "1_1") (pintype "passive"))
      (node (ref "C28") (pin "1") (pinfunction "1_1") (pintype "passive"))
      (node (ref "C29") (pin "2") (pinfunction "2_2") (pintype "passive"))
      (node (ref "C3") (pin "2") (pinfunction "2_2") (pintype "passive"))
      (node (ref "C30") (pin "2") (pinfunction "2_2") (pintype "passive"))
      (node (ref "C31") (pin "2") (pinfunction "2_2") (pintype "passive"))
      (node (ref "C32") (pin "2") (pinfunction "2_2") (pintype "passive"))
      (node (ref "C33") (pin "2") (pinfunction "2_2") (pintype "passive"))
      (node (ref "C34") (pin "2") (pinfunction "2_2") (pintype "passive"))
      (node (ref "C35") (pin "2") (pinfunction "2_2") (pintype "passive"))
      (node (ref "C36") (pin "2") (pinfunction "2_2") (pintype "passive"))
      (node (ref "C37") (pin "2") (pinfunction "2_2") (pintype "passive"))
      (node (ref "C38") (pin "2") (pinfunction "2_2") (pintype "passive"))
      (node (ref "C39") (pin "2") (pinfunction "2_2") (pintype "passive"))
      (node (ref "C4") (pin "2") (pinfunction "2_2") (pintype "passive"))
      (node (ref "C40") (pin "2") (pinfunction "2_2") (pintype "passive"))
      (node (ref "C41") (pin "2") (pinfunction "2_2") (pintype "passive"))
      (node (ref "C42") (pin "2") (pinfunction "2_2") (pintype "passive"))
      (node (ref "C43") (pin "2") (pinfunction "2_2") (pintype "passive"))
      (node (ref "C44") (pin "2") (pinfunction "2_2") (pintype "passive"))
      (node (ref "C45") (pin "2") (pinfunction "2_2") (pintype "passive"))
      (node (ref "C46") (pin "2") (pinfunction "2_2") (pintype "passive"))
      (node (ref "C47") (pin "2") (pinfunction "2_2") (pintype "passive"))
      (node (ref "C48") (pin "2") (pinfunction "2_2") (pintype "passive"))
      (node (ref "C49") (pin "2") (pinfunction "2_2") (pintype "passive"))
      (node (ref "C5") (pin "2") (pinfunction "2_2") (pintype "passive"))
      (node (ref "C50") (pin "2") (pinfunction "2_2") (pintype "passive"))
      (node (ref "C51") (pin "2") (pinfunction "2_2") (pintype "passive"))
      (node (ref "C52") (pin "2") (pinfunction "2_2") (pintype "passive"))
      (node (ref "C53") (pin "2") (pinfunction "2_2") (pintype "passive"))
      (node (ref "C54") (pin "2") (pinfunction "2_2") (pintype "passive"))
      (node (ref "C55") (pin "2") (pinfunction "2_2") (pintype "passive"))
      (node (ref "C56") (pin "2") (pinfunction "2_2") (pintype "passive"))
      (node (ref "C57") (pin "2") (pinfunction "2_2") (pintype "passive"))
      (node (ref "C58") (pin "2") (pinfunction "2_2") (pintype "passive"))
      (node (ref "C59") (pin "2") (pinfunction "2_2") (pintype "passive"))
      (node (ref "C6") (pin "2") (pinfunction "2_2") (pintype "passive"))
      (node (ref "C60") (pin "2") (pinfunction "2_2") (pintype "passive"))
      (node (ref "C61") (pin "2") (pinfunction "2_2") (pintype "passive"))
      (node (ref "C62") (pin "2") (pinfunction "2_2") (pintype "passive"))
      (node (ref "C63") (pin "2") (pinfunction "2_2") (pintype "passive"))
      (node (ref "C64") (pin "2") (pinfunction "2_2") (pintype "passive"))
      (node (ref "C65") (pin "2") (pinfunction "2_2") (pintype "passive"))
      (node (ref "C66") (pin "2") (pinfunction "2_2") (pintype "passive"))
      (node (ref "C67") (pin "2") (pinfunction "2_2") (pintype "passive"))
      (node (ref "C68") (pin "2") (pinfunction "2_2") (pintype "passive"))
      (node (ref "C69") (pin "2") (pinfunction "2_2") (pintype "passive"))
      (node (ref "C7") (pin "2") (pinfunction "2_2") (pintype "passive"))
      (node (ref "C70") (pin "2") (pinfunction "2_2") (pintype "passive"))
      (node (ref "C71") (pin "2") (pinfunction "2_2") (pintype "passive"))
      (node (ref "C72") (pin "2") (pinfunction "2_2") (pintype "passive"))
      (node (ref "C73") (pin "2") (pinfunction "2_2") (pintype "passive"))
      (node (ref "C74") (pin "2") (pinfunction "2_2") (pintype "passive"))
      (node (ref "C75") (pin "2") (pinfunction "2_2") (pintype "passive"))
      (node (ref "C76") (pin "2") (pinfunction "2_2") (pintype "passive"))
      (node (ref "C77") (pin "2") (pinfunction "2_2") (pintype "passive"))
      (node (ref "C78") (pin "2") (pinfunction "2_2") (pintype "passive"))
      (node (ref "C79") (pin "2") (pinfunction "2_2") (pintype "passive"))
      (node (ref "C8") (pin "2") (pinfunction "2_2") (pintype "passive"))
      (node (ref "C80") (pin "2") (pinfunction "2_2") (pintype "passive"))
      (node (ref "C81") (pin "2") (pinfunction "2_2") (pintype "passive"))
      (node (ref "C82") (pin "2") (pinfunction "2_2") (pintype "passive"))
      (node (ref "C83") (pin "2") (pinfunction "2_2") (pintype "passive"))
      (node (ref "C84") (pin "2") (pinfunction "2_2") (pintype "passive"))
      (node (ref "C85") (pin "2") (pinfunction "2_2") (pintype "passive"))
      (node (ref "C86") (pin "2") (pinfunction "2_2") (pintype "passive"))
      (node (ref "C87") (pin "2") (pinfunction "2_2") (pintype "passive"))
      (node (ref "C88") (pin "2") (pinfunction "2_2") (pintype "passive"))
      (node (ref "C89") (pin "2") (pinfunction "2_2") (pintype "passive"))
      (node (ref "C9") (pin "2") (pinfunction "2_2") (pintype "passive"))
      (node (ref "C90") (pin "2") (pinfunction "2_2") (pintype "passive"))
      (node (ref "C91") (pin "1") (pinfunction "1_1") (pintype "passive"))
      (node (ref "C92") (pin "2") (pinfunction "2_2") (pintype "passive"))
      (node (ref "C93") (pin "2") (pinfunction "2_2") (pintype "passive"))
      (node (ref "GND") (pin "TP") (pinfunction "TP_TP") (pintype "input"))
      (node (ref "GND75") (pin "TP") (pinfunction "TP_TP") (pintype "input"))
      (node (ref "GND77") (pin "TP") (pinfunction "TP_TP") (pintype "input"))
      (node (ref "R12") (pin "2") (pinfunction "2_2") (pintype "passive"))
      (node (ref "R15") (pin "2") (pinfunction "2_2") (pintype "passive"))
      (node (ref "R18") (pin "2") (pinfunction "2_2") (pintype "passive"))
      (node (ref "R22") (pin "1") (pinfunction "1_1") (pintype "passive"))
      (node (ref "R2X") (pin "2") (pinfunction "2_2") (pintype "passive"))
      (node (ref "R3") (pin "2") (pinfunction "2_2") (pintype "passive"))
      (node (ref "R6") (pin "2") (pinfunction "2_2") (pintype "passive"))
      (node (ref "R9") (pin "2") (pinfunction "2_2") (pintype "passive"))
      (node (ref "SENSOR") (pin "A21") (pinfunction "GND_A21") (pintype "power_in"))
      (node (ref "SENSOR") (pin "A25") (pinfunction "GND_A25") (pintype "power_in"))
      (node (ref "SENSOR") (pin "A28") (pinfunction "GND_A28") (pintype "power_in"))
      (node (ref "SENSOR") (pin "A29") (pinfunction "GND_A29") (pintype "power_in"))
      (node (ref "SENSOR") (pin "A9") (pinfunction "GND_A9") (pintype "power_in"))
      (node (ref "SENSOR") (pin "B22") (pinfunction "GND_B22") (pintype "power_in"))
      (node (ref "SENSOR") (pin "B26") (pinfunction "GND_B26") (pintype "power_in"))
      (node (ref "SENSOR") (pin "B27") (pinfunction "GND_B27") (pintype "power_in"))
      (node (ref "SENSOR") (pin "B28") (pinfunction "GND_B28") (pintype "power_in"))
      (node (ref "SENSOR") (pin "B5") (pinfunction "GND_B5") (pintype "power_in"))
      (node (ref "SENSOR") (pin "C15") (pinfunction "GND_C15") (pintype "power_in"))
      (node (ref "SENSOR") (pin "C16") (pinfunction "GND_C16") (pintype "power_in"))
      (node (ref "SENSOR") (pin "C28") (pinfunction "GND_C28") (pintype "power_in"))
      (node (ref "SENSOR") (pin "D2") (pinfunction "GND_D2") (pintype "power_in"))
      (node (ref "SENSOR") (pin "D25") (pinfunction "GND_D25") (pintype "power_in"))
      (node (ref "SENSOR") (pin "D27") (pinfunction "GND_D27") (pintype "power_in"))
      (node (ref "SENSOR") (pin "D29") (pinfunction "GND_D29") (pintype "power_in"))
      (node (ref "SENSOR") (pin "E15") (pinfunction "GND_E15") (pintype "power_in"))
      (node (ref "SENSOR") (pin "E16") (pinfunction "GND_E16") (pintype "power_in"))
      (node (ref "SENSOR") (pin "E25") (pinfunction "GND_E25") (pintype "power_in"))
      (node (ref "SENSOR") (pin "E27") (pinfunction "GND_E27") (pintype "power_in"))
      (node (ref "SENSOR") (pin "E3") (pinfunction "GND_E3") (pintype "power_in"))
      (node (ref "SENSOR") (pin "E4") (pinfunction "DIO2_E4") (pintype "output"))
      (node (ref "SENSOR") (pin "F27") (pinfunction "GND_F27") (pintype "power_in"))
      (node (ref "SENSOR") (pin "F4") (pinfunction "DIO1_F4") (pintype "output"))
      (node (ref "SENSOR") (pin "G3") (pinfunction "DIO4_G3") (pintype "output"))
      (node (ref "SENSOR") (pin "G5") (pinfunction "GND_G5") (pintype "power_in"))
      (node (ref "SENSOR") (pin "H1") (pinfunction "GND_H1") (pintype "power_in"))
      (node (ref "SENSOR") (pin "H21") (pinfunction "GND_H21") (pintype "power_in"))
      (node (ref "SENSOR") (pin "H25") (pinfunction "GND_H25") (pintype "power_in"))
      (node (ref "SENSOR") (pin "H27") (pinfunction "GND_H27") (pintype "power_in"))
      (node (ref "SENSOR") (pin "H4") (pinfunction "DIO3_H4") (pintype "output"))
      (node (ref "SENSOR") (pin "H6") (pinfunction "GND_H6") (pintype "power_in"))
      (node (ref "SENSOR") (pin "H9") (pinfunction "GND_H9") (pintype "power_in"))
      (node (ref "U1") (pin "6") (pinfunction "ANODE_6") (pintype "input"))
      (node (ref "U2") (pin "6") (pinfunction "ANODE_6") (pintype "input"))
      (node (ref "U3") (pin "2") (pinfunction "GND_2") (pintype "power_in"))
      (node (ref "U3") (pin "EP") (pinfunction "EP_EP") (pintype "power_in"))
      (node (ref "U4") (pin "16") (pinfunction "DIR2_16") (pintype "input"))
      (node (ref "U4") (pin "7") (pinfunction "~{OE}_7") (pintype "input"))
      (node (ref "U4") (pin "8") (pinfunction "GND_8") (pintype "passive"))
      (node (ref "U5") (pin "6") (pinfunction "DIR4_6") (pintype "input"))
      (node (ref "U5") (pin "7") (pinfunction "~{OE}_7") (pintype "input"))
      (node (ref "U5") (pin "8") (pinfunction "GND_8") (pintype "passive"))
      (node (ref "U6") (pin "16") (pinfunction "DIR2_16") (pintype "input"))
      (node (ref "U6") (pin "7") (pinfunction "~{OE}_7") (pintype "input"))
      (node (ref "U6") (pin "8") (pinfunction "GND_8") (pintype "passive"))
      (node (ref "U7") (pin "4") (pinfunction "GND_4") (pintype "power_in"))
      (node (ref "U7") (pin "5") (pinfunction "A2_5") (pintype "input"))
      (node (ref "U7") (pin "6") (pinfunction "A1_6") (pintype "input"))
      (node (ref "U7") (pin "7") (pinfunction "A0_7") (pintype "input"))
      (node (ref "UEP") (pin "1") (pinfunction "A0_1") (pintype "input"))
      (node (ref "UEP") (pin "2") (pinfunction "A1_2") (pintype "input"))
      (node (ref "UEP") (pin "3") (pinfunction "A2_3") (pintype "input"))
      (node (ref "UEP") (pin "4") (pinfunction "GND_4") (pintype "passive"))
      (node (ref "UEP") (pin "EP") (pinfunction "EP_EP") (pintype "passive"))
      (node (ref "UNE") (pin "4") (pinfunction "VSS_4") (pintype "power_in"))
      (node (ref "UNE") (pin "EP") (pinfunction "EP_EP") (pintype "passive"))
      (node (ref "UNN") (pin "4") (pinfunction "VSS_4") (pintype "power_in"))
      (node (ref "UNN") (pin "EP") (pinfunction "EP_EP") (pintype "passive"))
      (node (ref "UNW") (pin "4") (pinfunction "VSS_4") (pintype "power_in"))
      (node (ref "UNW") (pin "EP") (pinfunction "EP_EP") (pintype "passive"))
      (node (ref "USE") (pin "4") (pinfunction "VSS_4") (pintype "power_in"))
      (node (ref "USE") (pin "EP") (pinfunction "EP_EP") (pintype "passive"))
      (node (ref "USS") (pin "4") (pinfunction "VSS_4") (pintype "power_in"))
      (node (ref "USS") (pin "EP") (pinfunction "EP_EP") (pintype "passive"))
      (node (ref "USW") (pin "4") (pinfunction "VSS_4") (pintype "power_in"))
      (node (ref "USW") (pin "EP") (pinfunction "EP_EP") (pintype "passive"))
      (node (ref "X-NORTH") (pin "102") (pinfunction "102_102") (pintype "bidirectional"))
      (node (ref "X-NORTH") (pin "103") (pinfunction "103_103") (pintype "bidirectional"))
      (node (ref "X-NORTH") (pin "108") (pinfunction "108_108") (pintype "bidirectional"))
      (node (ref "X-NORTH") (pin "114") (pinfunction "114_114") (pintype "bidirectional"))
      (node (ref "X-NORTH") (pin "12") (pinfunction "12_12") (pintype "bidirectional"))
      (node (ref "X-NORTH") (pin "120") (pinfunction "120_120") (pintype "bidirectional"))
      (node (ref "X-NORTH") (pin "126") (pinfunction "126_126") (pintype "bidirectional"))
      (node (ref "X-NORTH") (pin "132") (pinfunction "132_132") (pintype "bidirectional"))
      (node (ref "X-NORTH") (pin "138") (pinfunction "138_138") (pintype "bidirectional"))
      (node (ref "X-NORTH") (pin "139") (pinfunction "139_139") (pintype "bidirectional"))
      (node (ref "X-NORTH") (pin "18") (pinfunction "18_18") (pintype "bidirectional"))
      (node (ref "X-NORTH") (pin "24") (pinfunction "24_24") (pintype "bidirectional"))
      (node (ref "X-NORTH") (pin "30") (pinfunction "30_30") (pintype "bidirectional"))
      (node (ref "X-NORTH") (pin "36") (pinfunction "36_36") (pintype "bidirectional"))
      (node (ref "X-NORTH") (pin "42") (pinfunction "42_42") (pintype "bidirectional"))
      (node (ref "X-NORTH") (pin "43") (pinfunction "43_43") (pintype "bidirectional"))
      (node (ref "X-NORTH") (pin "48") (pinfunction "48_48") (pintype "bidirectional"))
      (node (ref "X-NORTH") (pin "54") (pinfunction "54_54") (pintype "bidirectional"))
      (node (ref "X-NORTH") (pin "60") (pinfunction "60_60") (pintype "bidirectional"))
      (node (ref "X-NORTH") (pin "66") (pinfunction "66_66") (pintype "bidirectional"))
      (node (ref "X-NORTH") (pin "72") (pinfunction "72_72") (pintype "bidirectional"))
      (node (ref "X-NORTH") (pin "78") (pinfunction "78_78") (pintype "bidirectional"))
      (node (ref "X-NORTH") (pin "84") (pinfunction "84_84") (pintype "bidirectional"))
      (node (ref "X-NORTH") (pin "90") (pinfunction "90_90") (pintype "bidirectional"))
      (node (ref "X-NORTH") (pin "96") (pinfunction "96_96") (pintype "bidirectional"))
      (node (ref "X-SOUTH") (pin "102") (pinfunction "102_102") (pintype "bidirectional"))
      (node (ref "X-SOUTH") (pin "103") (pinfunction "103_103") (pintype "bidirectional"))
      (node (ref "X-SOUTH") (pin "108") (pinfunction "108_108") (pintype "bidirectional"))
      (node (ref "X-SOUTH") (pin "114") (pinfunction "114_114") (pintype "bidirectional"))
      (node (ref "X-SOUTH") (pin "12") (pinfunction "12_12") (pintype "bidirectional"))
      (node (ref "X-SOUTH") (pin "120") (pinfunction "120_120") (pintype "bidirectional"))
      (node (ref "X-SOUTH") (pin "126") (pinfunction "126_126") (pintype "bidirectional"))
      (node (ref "X-SOUTH") (pin "132") (pinfunction "132_132") (pintype "bidirectional"))
      (node (ref "X-SOUTH") (pin "138") (pinfunction "138_138") (pintype "bidirectional"))
      (node (ref "X-SOUTH") (pin "139") (pinfunction "139_139") (pintype "bidirectional"))
      (node (ref "X-SOUTH") (pin "18") (pinfunction "18_18") (pintype "bidirectional"))
      (node (ref "X-SOUTH") (pin "24") (pinfunction "24_24") (pintype "bidirectional"))
      (node (ref "X-SOUTH") (pin "30") (pinfunction "30_30") (pintype "bidirectional"))
      (node (ref "X-SOUTH") (pin "36") (pinfunction "36_36") (pintype "bidirectional"))
      (node (ref "X-SOUTH") (pin "42") (pinfunction "42_42") (pintype "bidirectional"))
      (node (ref "X-SOUTH") (pin "43") (pinfunction "43_43") (pintype "bidirectional"))
      (node (ref "X-SOUTH") (pin "48") (pinfunction "48_48") (pintype "bidirectional"))
      (node (ref "X-SOUTH") (pin "54") (pinfunction "54_54") (pintype "bidirectional"))
      (node (ref "X-SOUTH") (pin "60") (pinfunction "60_60") (pintype "bidirectional"))
      (node (ref "X-SOUTH") (pin "66") (pinfunction "66_66") (pintype "bidirectional"))
      (node (ref "X-SOUTH") (pin "72") (pinfunction "72_72") (pintype "bidirectional"))
      (node (ref "X-SOUTH") (pin "78") (pinfunction "78_78") (pintype "bidirectional"))
      (node (ref "X-SOUTH") (pin "84") (pinfunction "84_84") (pintype "bidirectional"))
      (node (ref "X-SOUTH") (pin "90") (pinfunction "90_90") (pintype "bidirectional"))
      (node (ref "X-SOUTH") (pin "96") (pinfunction "96_96") (pintype "bidirectional"))
    )
    (net (code "4") (name "N$42") (class "Default")
      (node (ref "SENSOR") (pin "A2") (pinfunction "TANA_A2") (pintype "output"))
    )
    (net (code "5") (name "N00_N") (class "Default")
      (node (ref "R25") (pin "2") (pinfunction "2_2") (pintype "passive"))
      (node (ref "SENSOR") (pin "E6") (pinfunction "LVDS_CLK_P_E6") (pintype "input"))
      (node (ref "X-NORTH") (pin "16") (pinfunction "16_16") (pintype "bidirectional"))
    )
    (net (code "6") (name "N00_P") (class "Default")
      (node (ref "R25") (pin "1") (pinfunction "1_1") (pintype "passive"))
      (node (ref "SENSOR") (pin "E5") (pinfunction "LVDS_CLK_N_E5") (pintype "input"))
      (node (ref "X-NORTH") (pin "14") (pinfunction "14_14") (pintype "bidirectional"))
    )
    (net (code "7") (name "N01_N") (class "Default")
      (node (ref "SENSOR") (pin "G7") (pinfunction "OUTCLK_P_G7") (pintype "output"))
      (node (ref "X-NORTH") (pin "17") (pinfunction "17_17") (pintype "bidirectional"))
    )
    (net (code "8") (name "N01_P") (class "Default")
      (node (ref "SENSOR") (pin "G6") (pinfunction "OUTCLK_N_G6") (pintype "output"))
      (node (ref "X-NORTH") (pin "15") (pinfunction "15_15") (pintype "bidirectional"))
    )
    (net (code "9") (name "N02_N") (class "Default")
      (node (ref "SENSOR") (pin "F7") (pinfunction "OUT33_P_F7") (pintype "output"))
      (node (ref "X-NORTH") (pin "22") (pinfunction "22_22") (pintype "bidirectional"))
    )
    (net (code "10") (name "N02_P") (class "Default")
      (node (ref "SENSOR") (pin "F6") (pinfunction "OUT33_N_F6") (pintype "output"))
      (node (ref "X-NORTH") (pin "20") (pinfunction "20_20") (pintype "bidirectional"))
    )
    (net (code "11") (name "N03_N") (class "Default")
      (node (ref "X-NORTH") (pin "23") (pinfunction "23_23") (pintype "bidirectional"))
    )
    (net (code "12") (name "N03_P") (class "Default")
      (node (ref "X-NORTH") (pin "21") (pinfunction "21_21") (pintype "bidirectional"))
    )
    (net (code "13") (name "N04_N") (class "Default")
      (node (ref "SENSOR") (pin "E8") (pinfunction "OUT35_P_E8") (pintype "output"))
      (node (ref "X-NORTH") (pin "28") (pinfunction "28_28") (pintype "bidirectional"))
    )
    (net (code "14") (name "N04_P") (class "Default")
      (node (ref "SENSOR") (pin "E7") (pinfunction "OUT35_N_E7") (pintype "output"))
      (node (ref "X-NORTH") (pin "26") (pinfunction "26_26") (pintype "bidirectional"))
    )
    (net (code "15") (name "N05_N") (class "Default")
      (node (ref "SENSOR") (pin "H8") (pinfunction "OUT34_P_H8") (pintype "output"))
      (node (ref "X-NORTH") (pin "29") (pinfunction "29_29") (pintype "bidirectional"))
    )
    (net (code "16") (name "N05_P") (class "Default")
      (node (ref "SENSOR") (pin "H7") (pinfunction "OUT34_N_H7") (pintype "output"))
      (node (ref "X-NORTH") (pin "27") (pinfunction "27_27") (pintype "bidirectional"))
    )
    (net (code "17") (name "N06_N") (class "Default")
      (node (ref "SENSOR") (pin "F9") (pinfunction "OUT37_P_F9") (pintype "output"))
      (node (ref "X-NORTH") (pin "34") (pinfunction "34_34") (pintype "bidirectional"))
    )
    (net (code "18") (name "N06_P") (class "Default")
      (node (ref "SENSOR") (pin "F8") (pinfunction "OUT37_N_F8") (pintype "output"))
      (node (ref "X-NORTH") (pin "32") (pinfunction "32_32") (pintype "bidirectional"))
    )
    (net (code "19") (name "N07_N") (class "Default")
      (node (ref "SENSOR") (pin "G9") (pinfunction "OUT36_P_G9") (pintype "output"))
      (node (ref "X-NORTH") (pin "35") (pinfunction "35_35") (pintype "bidirectional"))
    )
    (net (code "20") (name "N07_P") (class "Default")
      (node (ref "SENSOR") (pin "G8") (pinfunction "OUT36_N_G8") (pintype "output"))
      (node (ref "X-NORTH") (pin "33") (pinfunction "33_33") (pintype "bidirectional"))
    )
    (net (code "21") (name "N08_N") (class "Default")
      (node (ref "SENSOR") (pin "E10") (pinfunction "OUT38_P_E10") (pintype "output"))
      (node (ref "X-NORTH") (pin "40") (pinfunction "40_40") (pintype "bidirectional"))
    )
    (net (code "22") (name "N08_P") (class "Default")
      (node (ref "SENSOR") (pin "E9") (pinfunction "OUT38_N_E9") (pintype "output"))
      (node (ref "X-NORTH") (pin "38") (pinfunction "38_38") (pintype "bidirectional"))
    )
    (net (code "23") (name "N09_N") (class "Default")
      (node (ref "SENSOR") (pin "G11") (pinfunction "OUT39_P_G11") (pintype "output"))
      (node (ref "X-NORTH") (pin "41") (pinfunction "41_41") (pintype "bidirectional"))
    )
    (net (code "24") (name "N09_P") (class "Default")
      (node (ref "SENSOR") (pin "G10") (pinfunction "OUT39_N_G10") (pintype "output"))
      (node (ref "X-NORTH") (pin "39") (pinfunction "39_39") (pintype "bidirectional"))
    )
    (net (code "25") (name "N10_N") (class "Default")
      (node (ref "SENSOR") (pin "F11") (pinfunction "OUT40_P_F11") (pintype "output"))
      (node (ref "X-NORTH") (pin "46") (pinfunction "46_46") (pintype "bidirectional"))
    )
    (net (code "26") (name "N10_P") (class "Default")
      (node (ref "SENSOR") (pin "F10") (pinfunction "OUT40_N_F10") (pintype "output"))
      (node (ref "X-NORTH") (pin "44") (pinfunction "44_44") (pintype "bidirectional"))
    )
    (net (code "27") (name "N11_N") (class "Default")
      (node (ref "SENSOR") (pin "H12") (pinfunction "OUT41_P_H12") (pintype "output"))
      (node (ref "X-NORTH") (pin "47") (pinfunction "47_47") (pintype "bidirectional"))
    )
    (net (code "28") (name "N11_P") (class "Default")
      (node (ref "SENSOR") (pin "H11") (pinfunction "OUT41_N_H11") (pintype "output"))
      (node (ref "X-NORTH") (pin "45") (pinfunction "45_45") (pintype "bidirectional"))
    )
    (net (code "29") (name "N12_N") (class "Default")
      (node (ref "SENSOR") (pin "E12") (pinfunction "OUT42_P_E12") (pintype "output"))
      (node (ref "X-NORTH") (pin "52") (pinfunction "52_52") (pintype "bidirectional"))
    )
    (net (code "30") (name "N12_P") (class "Default")
      (node (ref "SENSOR") (pin "E11") (pinfunction "OUT42_N_E11") (pintype "output"))
      (node (ref "X-NORTH") (pin "50") (pinfunction "50_50") (pintype "bidirectional"))
    )
    (net (code "31") (name "N13_N") (class "Default")
      (node (ref "SENSOR") (pin "G13") (pinfunction "OUT43_P_G13") (pintype "output"))
      (node (ref "X-NORTH") (pin "53") (pinfunction "53_53") (pintype "bidirectional"))
    )
    (net (code "32") (name "N13_P") (class "Default")
      (node (ref "SENSOR") (pin "G12") (pinfunction "OUT43_N_G12") (pintype "output"))
      (node (ref "X-NORTH") (pin "51") (pinfunction "51_51") (pintype "bidirectional"))
    )
    (net (code "33") (name "N14_N") (class "Default")
      (node (ref "SENSOR") (pin "F13") (pinfunction "OUT44_P_F13") (pintype "output"))
      (node (ref "X-NORTH") (pin "58") (pinfunction "58_58") (pintype "bidirectional"))
    )
    (net (code "34") (name "N14_P") (class "Default")
      (node (ref "SENSOR") (pin "F12") (pinfunction "OUT44_N_F12") (pintype "output"))
      (node (ref "X-NORTH") (pin "56") (pinfunction "56_56") (pintype "bidirectional"))
    )
    (net (code "35") (name "N15_N") (class "Default")
      (node (ref "SENSOR") (pin "H14") (pinfunction "OUT45_P_H14") (pintype "output"))
      (node (ref "X-NORTH") (pin "59") (pinfunction "59_59") (pintype "bidirectional"))
    )
    (net (code "36") (name "N15_P") (class "Default")
      (node (ref "SENSOR") (pin "H13") (pinfunction "OUT45_N_H13") (pintype "output"))
      (node (ref "X-NORTH") (pin "57") (pinfunction "57_57") (pintype "bidirectional"))
    )
    (net (code "37") (name "N16_N") (class "Default")
      (node (ref "SENSOR") (pin "E14") (pinfunction "OUT46_P_E14") (pintype "output"))
      (node (ref "X-NORTH") (pin "64") (pinfunction "64_64") (pintype "bidirectional"))
    )
    (net (code "38") (name "N16_P") (class "Default")
      (node (ref "SENSOR") (pin "E13") (pinfunction "OUT46_N_E13") (pintype "output"))
      (node (ref "X-NORTH") (pin "62") (pinfunction "62_62") (pintype "bidirectional"))
    )
    (net (code "39") (name "N17_N") (class "Default")
      (node (ref "SENSOR") (pin "G15") (pinfunction "OUT47_P_G15") (pintype "output"))
      (node (ref "X-NORTH") (pin "65") (pinfunction "65_65") (pintype "bidirectional"))
    )
    (net (code "40") (name "N17_P") (class "Default")
      (node (ref "SENSOR") (pin "G14") (pinfunction "OUT47_N_G14") (pintype "output"))
      (node (ref "X-NORTH") (pin "63") (pinfunction "63_63") (pintype "bidirectional"))
    )
    (net (code "41") (name "N18_N") (class "Default")
      (node (ref "SENSOR") (pin "F15") (pinfunction "OUT48_P_F15") (pintype "output"))
      (node (ref "X-NORTH") (pin "70") (pinfunction "70_70") (pintype "bidirectional"))
    )
    (net (code "42") (name "N18_P") (class "Default")
      (node (ref "SENSOR") (pin "F14") (pinfunction "OUT48_N_F14") (pintype "output"))
      (node (ref "X-NORTH") (pin "68") (pinfunction "68_68") (pintype "bidirectional"))
    )
    (net (code "43") (name "N19_N") (class "Default")
      (node (ref "SENSOR") (pin "G17") (pinfunction "OUT50_P_G17") (pintype "output"))
      (node (ref "X-NORTH") (pin "71") (pinfunction "71_71") (pintype "bidirectional"))
    )
    (net (code "44") (name "N19_P") (class "Default")
      (node (ref "SENSOR") (pin "G16") (pinfunction "OUT50_N_G16") (pintype "output"))
      (node (ref "X-NORTH") (pin "69") (pinfunction "69_69") (pintype "bidirectional"))
    )
    (net (code "45") (name "N20_N") (class "Default")
      (node (ref "SENSOR") (pin "F17") (pinfunction "OUT49_P_F17") (pintype "output"))
      (node (ref "X-NORTH") (pin "76") (pinfunction "76_76") (pintype "bidirectional"))
    )
    (net (code "46") (name "N20_P") (class "Default")
      (node (ref "SENSOR") (pin "F16") (pinfunction "OUT49_N_F16") (pintype "output"))
      (node (ref "X-NORTH") (pin "74") (pinfunction "74_74") (pintype "bidirectional"))
    )
    (net (code "47") (name "N21_N") (class "Default")
      (node (ref "SENSOR") (pin "H18") (pinfunction "OUT52_P_H18") (pintype "output"))
      (node (ref "X-NORTH") (pin "77") (pinfunction "77_77") (pintype "bidirectional"))
    )
    (net (code "48") (name "N21_P") (class "Default")
      (node (ref "SENSOR") (pin "H17") (pinfunction "OUT52_N_H17") (pintype "output"))
      (node (ref "X-NORTH") (pin "75") (pinfunction "75_75") (pintype "bidirectional"))
    )
    (net (code "49") (name "N22_N") (class "Default")
      (node (ref "SENSOR") (pin "E18") (pinfunction "OUT51_P_E18") (pintype "output"))
      (node (ref "X-NORTH") (pin "82") (pinfunction "82_82") (pintype "bidirectional"))
    )
    (net (code "50") (name "N22_P") (class "Default")
      (node (ref "SENSOR") (pin "E17") (pinfunction "OUT51_N_E17") (pintype "output"))
      (node (ref "X-NORTH") (pin "80") (pinfunction "80_80") (pintype "bidirectional"))
    )
    (net (code "51") (name "N23_N") (class "Default")
      (node (ref "SENSOR") (pin "G19") (pinfunction "OUT54_P_G19") (pintype "output"))
      (node (ref "X-NORTH") (pin "83") (pinfunction "83_83") (pintype "bidirectional"))
    )
    (net (code "52") (name "N23_P") (class "Default")
      (node (ref "SENSOR") (pin "G18") (pinfunction "OUT54_N_G18") (pintype "output"))
      (node (ref "X-NORTH") (pin "81") (pinfunction "81_81") (pintype "bidirectional"))
    )
    (net (code "53") (name "N24_N") (class "Default")
      (node (ref "SENSOR") (pin "F19") (pinfunction "OUT53_P_F19") (pintype "output"))
      (node (ref "X-NORTH") (pin "88") (pinfunction "88_88") (pintype "bidirectional"))
    )
    (net (code "54") (name "N24_P") (class "Default")
      (node (ref "SENSOR") (pin "F18") (pinfunction "OUT53_N_F18") (pintype "output"))
      (node (ref "X-NORTH") (pin "86") (pinfunction "86_86") (pintype "bidirectional"))
    )
    (net (code "55") (name "N25_N") (class "Default")
      (node (ref "SENSOR") (pin "H20") (pinfunction "OUT56_P_H20") (pintype "output"))
      (node (ref "X-NORTH") (pin "89") (pinfunction "89_89") (pintype "bidirectional"))
    )
    (net (code "56") (name "N25_P") (class "Default")
      (node (ref "SENSOR") (pin "H19") (pinfunction "OUT56_N_H19") (pintype "output"))
      (node (ref "X-NORTH") (pin "87") (pinfunction "87_87") (pintype "bidirectional"))
    )
    (net (code "57") (name "N26_N") (class "Default")
      (node (ref "SENSOR") (pin "E20") (pinfunction "OUT55_P_E20") (pintype "output"))
      (node (ref "X-NORTH") (pin "94") (pinfunction "94_94") (pintype "bidirectional"))
    )
    (net (code "58") (name "N26_P") (class "Default")
      (node (ref "SENSOR") (pin "E19") (pinfunction "OUT55_N_E19") (pintype "output"))
      (node (ref "X-NORTH") (pin "92") (pinfunction "92_92") (pintype "bidirectional"))
    )
    (net (code "59") (name "N27_N") (class "Default")
      (node (ref "SENSOR") (pin "G21") (pinfunction "OUT58_P_G21") (pintype "output"))
      (node (ref "X-NORTH") (pin "95") (pinfunction "95_95") (pintype "bidirectional"))
    )
    (net (code "60") (name "N27_P") (class "Default")
      (node (ref "SENSOR") (pin "G20") (pinfunction "OUT58_N_G20") (pintype "output"))
      (node (ref "X-NORTH") (pin "93") (pinfunction "93_93") (pintype "bidirectional"))
    )
    (net (code "61") (name "N28_N") (class "Default")
      (node (ref "SENSOR") (pin "F21") (pinfunction "OUT57_P_F21") (pintype "output"))
      (node (ref "X-NORTH") (pin "100") (pinfunction "100_100") (pintype "bidirectional"))
    )
    (net (code "62") (name "N28_P") (class "Default")
      (node (ref "SENSOR") (pin "F20") (pinfunction "OUT57_N_F20") (pintype "output"))
      (node (ref "X-NORTH") (pin "98") (pinfunction "98_98") (pintype "bidirectional"))
    )
    (net (code "63") (name "N29_N") (class "Default")
      (node (ref "SENSOR") (pin "G23") (pinfunction "OUT61_P_G23") (pintype "output"))
      (node (ref "X-NORTH") (pin "101") (pinfunction "101_101") (pintype "bidirectional"))
    )
    (net (code "64") (name "N29_P") (class "Default")
      (node (ref "SENSOR") (pin "G22") (pinfunction "OUT61_N_G22") (pintype "output"))
      (node (ref "X-NORTH") (pin "99") (pinfunction "99_99") (pintype "bidirectional"))
    )
    (net (code "65") (name "N30_N") (class "Default")
      (node (ref "SENSOR") (pin "E22") (pinfunction "OUT59_P_E22") (pintype "output"))
      (node (ref "X-NORTH") (pin "106") (pinfunction "106_106") (pintype "bidirectional"))
    )
    (net (code "66") (name "N30_P") (class "Default")
      (node (ref "SENSOR") (pin "E21") (pinfunction "OUT59_N_E21") (pintype "output"))
      (node (ref "X-NORTH") (pin "104") (pinfunction "104_104") (pintype "bidirectional"))
    )
    (net (code "67") (name "N31_N") (class "Default")
      (node (ref "SENSOR") (pin "H24") (pinfunction "OUT63_P_H24") (pintype "output"))
      (node (ref "X-NORTH") (pin "107") (pinfunction "107_107") (pintype "bidirectional"))
    )
    (net (code "68") (name "N31_P") (class "Default")
      (node (ref "SENSOR") (pin "H23") (pinfunction "OUT63_N_H23") (pintype "output"))
      (node (ref "X-NORTH") (pin "105") (pinfunction "105_105") (pintype "bidirectional"))
    )
    (net (code "69") (name "N32_N") (class "Default")
      (node (ref "SENSOR") (pin "F23") (pinfunction "OUT60_P_F23") (pintype "output"))
      (node (ref "X-NORTH") (pin "112") (pinfunction "112_112") (pintype "bidirectional"))
    )
    (net (code "70") (name "N32_P") (class "Default")
      (node (ref "SENSOR") (pin "F22") (pinfunction "OUT60_N_F22") (pintype "output"))
      (node (ref "X-NORTH") (pin "110") (pinfunction "110_110") (pintype "bidirectional"))
    )
    (net (code "71") (name "N33_N") (class "Default")
      (node (ref "SENSOR") (pin "G25") (pinfunction "OUT64_P_G25") (pintype "output"))
      (node (ref "X-NORTH") (pin "113") (pinfunction "113_113") (pintype "bidirectional"))
    )
    (net (code "72") (name "N33_P") (class "Default")
      (node (ref "SENSOR") (pin "G24") (pinfunction "OUT64_N_G24") (pintype "output"))
      (node (ref "X-NORTH") (pin "111") (pinfunction "111_111") (pintype "bidirectional"))
    )
    (net (code "73") (name "N34_N") (class "Default")
      (node (ref "SENSOR") (pin "E24") (pinfunction "OUT62_P_E24") (pintype "output"))
      (node (ref "X-NORTH") (pin "118") (pinfunction "118_118") (pintype "bidirectional"))
    )
    (net (code "74") (name "N34_P") (class "Default")
      (node (ref "SENSOR") (pin "E23") (pinfunction "OUT62_N_E23") (pintype "output"))
      (node (ref "X-NORTH") (pin "116") (pinfunction "116_116") (pintype "bidirectional"))
    )
    (net (code "75") (name "N35_N") (class "Default")
      (node (ref "U6") (pin "4") (pinfunction "A4_4") (pintype "bidirectional"))
      (node (ref "X-NORTH") (pin "119") (pinfunction "119_119") (pintype "bidirectional"))
    )
    (net (code "76") (name "N35_P") (class "Default")
      (node (ref "U6") (pin "3") (pinfunction "A3_3") (pintype "bidirectional"))
      (node (ref "X-NORTH") (pin "117") (pinfunction "117_117") (pintype "bidirectional"))
    )
    (net (code "77") (name "N36_N") (class "Default")
      (node (ref "X-NORTH") (pin "124") (pinfunction "124_124") (pintype "bidirectional"))
    )
    (net (code "78") (name "N36_P") (class "Default")
      (node (ref "X-NORTH") (pin "122") (pinfunction "122_122") (pintype "bidirectional"))
    )
    (net (code "79") (name "N37_N") (class "Default")
      (node (ref "U5") (pin "3") (pinfunction "A3_3") (pintype "bidirectional"))
      (node (ref "X-NORTH") (pin "125") (pinfunction "125_125") (pintype "bidirectional"))
    )
    (net (code "80") (name "N37_P") (class "Default")
      (node (ref "U5") (pin "4") (pinfunction "A4_4") (pintype "bidirectional"))
      (node (ref "X-NORTH") (pin "123") (pinfunction "123_123") (pintype "bidirectional"))
    )
    (net (code "81") (name "N38_N") (class "Default")
      (node (ref "U6") (pin "2") (pinfunction "A2_2") (pintype "bidirectional"))
      (node (ref "X-NORTH") (pin "130") (pinfunction "130_130") (pintype "bidirectional"))
    )
    (net (code "82") (name "N38_P") (class "Default")
      (node (ref "U6") (pin "1") (pinfunction "A1_1") (pintype "bidirectional"))
      (node (ref "X-NORTH") (pin "128") (pinfunction "128_128") (pintype "bidirectional"))
    )
    (net (code "83") (name "N39_N") (class "Default")
      (node (ref "U5") (pin "1") (pinfunction "A1_1") (pintype "bidirectional"))
      (node (ref "X-NORTH") (pin "131") (pinfunction "131_131") (pintype "bidirectional"))
    )
    (net (code "84") (name "N39_P") (class "Default")
      (node (ref "U5") (pin "2") (pinfunction "A2_2") (pintype "bidirectional"))
      (node (ref "X-NORTH") (pin "129") (pinfunction "129_129") (pintype "bidirectional"))
    )
    (net (code "85") (name "N_CHK_EN") (class "Default")
      (node (ref "X-NORTH") (pin "8") (pinfunction "8_8") (pintype "bidirectional"))
    )
    (net (code "86") (name "N_CHK_V") (class "Default")
      (node (ref "C2") (pin "1") (pinfunction "1_1") (pintype "passive"))
      (node (ref "C3") (pin "1") (pinfunction "1_1") (pintype "passive"))
      (node (ref "C4") (pin "1") (pinfunction "1_1") (pintype "passive"))
      (node (ref "R19") (pin "1") (pinfunction "1_1") (pintype "passive"))
      (node (ref "TP1") (pin "TP") (pinfunction "TP_TP") (pintype "input"))
      (node (ref "UNE") (pin "8") (pinfunction "VDD_8") (pintype "power_in"))
      (node (ref "UNN") (pin "8") (pinfunction "VDD_8") (pintype "power_in"))
      (node (ref "UNW") (pin "8") (pinfunction "VDD_8") (pintype "power_in"))
      (node (ref "X-NORTH") (pin "10") (pinfunction "10_10") (pintype "bidirectional"))
    )
    (net (code "87") (name "N_I2C_EN") (class "Default")
      (node (ref "X-NORTH") (pin "137") (pinfunction "137_137") (pintype "bidirectional"))
    )
    (net (code "88") (name "N_I2C_V") (class "Default")
      (node (ref "C1") (pin "1") (pinfunction "1_1") (pintype "passive"))
      (node (ref "R1X") (pin "1") (pinfunction "1_1") (pintype "passive"))
      (node (ref "UEP") (pin "8") (pinfunction "VCC_8") (pintype "power_in"))
      (node (ref "X-NORTH") (pin "135") (pinfunction "135_135") (pintype "bidirectional"))
    )
    (net (code "89") (name "N_REF") (class "Default")
      (node (ref "R19") (pin "2") (pinfunction "2_2") (pintype "passive"))
      (node (ref "TP2") (pin "TP") (pinfunction "TP_TP") (pintype "input"))
      (node (ref "U1") (pin "1") (pinfunction "CATHODE_1") (pintype "output"))
      (node (ref "U1") (pin "3") (pinfunction "REF_3") (pintype "input"))
      (node (ref "UNE") (pin "2") (pinfunction "VINA-_2") (pintype "input"))
      (node (ref "UNE") (pin "5") (pinfunction "VINB+_5") (pintype "input"))
      (node (ref "UNN") (pin "2") (pinfunction "VINA-_2") (pintype "input"))
      (node (ref "UNN") (pin "5") (pinfunction "VINB+_5") (pintype "input"))
      (node (ref "UNW") (pin "2") (pinfunction "VINA-_2") (pintype "input"))
      (node (ref "UNW") (pin "5") (pinfunction "VINB+_5") (pintype "input"))
    )
    (net (code "90") (name "N_SCK") (class "Default")
      (node (ref "U4") (pin "4") (pinfunction "A4_4") (pintype "bidirectional"))
      (node (ref "X-NORTH") (pin "144") (pinfunction "144_144") (pintype "bidirectional"))
    )
    (net (code "91") (name "N_SCL") (class "Default")
      (node (ref "UEP") (pin "6") (pinfunction "SCL_6") (pintype "input"))
      (node (ref "X-NORTH") (pin "143") (pinfunction "143_143") (pintype "bidirectional"))
    )
    (net (code "92") (name "N_SDA") (class "Default")
      (node (ref "UEP") (pin "5") (pinfunction "SDA_5") (pintype "bidirectional"))
      (node (ref "X-NORTH") (pin "141") (pinfunction "141_141") (pintype "bidirectional"))
    )
    (net (code "93") (name "N_SDI") (class "Default")
      (node (ref "U4") (pin "2") (pinfunction "A2_2") (pintype "bidirectional"))
      (node (ref "X-NORTH") (pin "140") (pinfunction "140_140") (pintype "bidirectional"))
    )
    (net (code "94") (name "N_SDO") (class "Default")
      (node (ref "U4") (pin "3") (pinfunction "A3_3") (pintype "bidirectional"))
      (node (ref "X-NORTH") (pin "142") (pinfunction "142_142") (pintype "bidirectional"))
    )
    (net (code "95") (name "N_SPI_EN") (class "Default")
      (node (ref "U4") (pin "1") (pinfunction "A1_1") (pintype "bidirectional"))
      (node (ref "X-NORTH") (pin "136") (pinfunction "136_136") (pintype "bidirectional"))
    )
    (net (code "96") (name "N_SPI_V") (class "Default")
      (node (ref "C59") (pin "1") (pinfunction "1_1") (pintype "passive"))
      (node (ref "U4") (pin "14") (pinfunction "VCCA_14") (pintype "power_in"))
      (node (ref "U4") (pin "15") (pinfunction "DIR1_15") (pintype "input"))
      (node (ref "U4") (pin "5") (pinfunction "DIR3_5") (pintype "input"))
      (node (ref "U4") (pin "6") (pinfunction "DIR4_6") (pintype "input"))
      (node (ref "X-NORTH") (pin "134") (pinfunction "134_134") (pintype "bidirectional"))
    )
    (net (code "97") (name "N_VE") (class "Default")
      (node (ref "C50") (pin "1") (pinfunction "1_1") (pintype "passive"))
      (node (ref "C51") (pin "1") (pinfunction "1_1") (pintype "passive"))
      (node (ref "C52") (pin "1") (pinfunction "1_1") (pintype "passive"))
      (node (ref "C53") (pin "1") (pinfunction "1_1") (pintype "passive"))
      (node (ref "C54") (pin "1") (pinfunction "1_1") (pintype "passive"))
      (node (ref "C55") (pin "1") (pinfunction "1_1") (pintype "passive"))
      (node (ref "C56") (pin "1") (pinfunction "1_1") (pintype "passive"))
      (node (ref "C67") (pin "1") (pinfunction "1_1") (pintype "passive"))
      (node (ref "C69") (pin "1") (pinfunction "1_1") (pintype "passive"))
      (node (ref "C75") (pin "1") (pinfunction "1_1") (pintype "passive"))
      (node (ref "C76") (pin "1") (pinfunction "1_1") (pintype "passive"))
      (node (ref "C77") (pin "1") (pinfunction "1_1") (pintype "passive"))
      (node (ref "C84") (pin "1") (pinfunction "1_1") (pintype "passive"))
      (node (ref "C85") (pin "1") (pinfunction "1_1") (pintype "passive"))
      (node (ref "C86") (pin "1") (pinfunction "1_1") (pintype "passive"))
      (node (ref "C93") (pin "1") (pinfunction "1_1") (pintype "passive"))
      (node (ref "SENSOR") (pin "C26") (pinfunction "VDD33_C26") (pintype "power_in"))
      (node (ref "SENSOR") (pin "C27") (pinfunction "VDD33_C27") (pintype "power_in"))
      (node (ref "SENSOR") (pin "D26") (pinfunction "VDD33_D26") (pintype "power_in"))
      (node (ref "SENSOR") (pin "D3") (pinfunction "VDD33_D3") (pintype "power_in"))
      (node (ref "SENSOR") (pin "E26") (pinfunction "VDD33_E26") (pintype "power_in"))
      (node (ref "SENSOR") (pin "F26") (pinfunction "VDD33_F26") (pintype "power_in"))
      (node (ref "SENSOR") (pin "F5") (pinfunction "VDD33_F5") (pintype "power_in"))
      (node (ref "TP7") (pin "TP") (pinfunction "TP_TP") (pintype "input"))
      (node (ref "U4") (pin "13") (pinfunction "VCCB_13") (pintype "power_in"))
      (node (ref "U5") (pin "13") (pinfunction "VCCB_13") (pintype "power_in"))
      (node (ref "U6") (pin "13") (pinfunction "VCCB_13") (pintype "power_in"))
      (node (ref "X-NORTH") (pin "109") (pinfunction "109_109") (pintype "bidirectional"))
      (node (ref "X-NORTH") (pin "115") (pinfunction "115_115") (pintype "bidirectional"))
      (node (ref "X-NORTH") (pin "121") (pinfunction "121_121") (pintype "bidirectional"))
      (node (ref "X-NORTH") (pin "127") (pinfunction "127_127") (pintype "bidirectional"))
      (node (ref "X-NORTH") (pin "133") (pinfunction "133_133") (pintype "bidirectional"))
    )
    (net (code "98") (name "N_VE_CV") (class "Default")
      (node (ref "C10") (pin "1") (pinfunction "1_1") (pintype "passive"))
      (node (ref "R7") (pin "1") (pinfunction "1_1") (pintype "passive"))
      (node (ref "X-NORTH") (pin "6") (pinfunction "6_6") (pintype "bidirectional"))
    )
    (net (code "99") (name "N_VE_OV") (class "Default")
      (node (ref "UNE") (pin "7") (pinfunction "OUTB_7") (pintype "output"))
      (node (ref "X-NORTH") (pin "5") (pinfunction "5_5") (pintype "bidirectional"))
    )
    (net (code "100") (name "N_VE_UV") (class "Default")
      (node (ref "UNE") (pin "1") (pinfunction "OUTA_1") (pintype "output"))
      (node (ref "X-NORTH") (pin "11") (pinfunction "11_11") (pintype "bidirectional"))
    )
    (net (code "101") (name "N_VN") (class "Default")
      (node (ref "C31") (pin "1") (pinfunction "1_1") (pintype "passive"))
      (node (ref "C32") (pin "1") (pinfunction "1_1") (pintype "passive"))
      (node (ref "C33") (pin "1") (pinfunction "1_1") (pintype "passive"))
      (node (ref "C34") (pin "1") (pinfunction "1_1") (pintype "passive"))
      (node (ref "C35") (pin "1") (pinfunction "1_1") (pintype "passive"))
      (node (ref "C36") (pin "1") (pinfunction "1_1") (pintype "passive"))
      (node (ref "C37") (pin "1") (pinfunction "1_1") (pintype "passive"))
      (node (ref "C38") (pin "1") (pinfunction "1_1") (pintype "passive"))
      (node (ref "C39") (pin "1") (pinfunction "1_1") (pintype "passive"))
      (node (ref "C40") (pin "1") (pinfunction "1_1") (pintype "passive"))
      (node (ref "C41") (pin "1") (pinfunction "1_1") (pintype "passive"))
      (node (ref "C42") (pin "1") (pinfunction "1_1") (pintype "passive"))
      (node (ref "C43") (pin "1") (pinfunction "1_1") (pintype "passive"))
      (node (ref "C44") (pin "1") (pinfunction "1_1") (pintype "passive"))
      (node (ref "C68") (pin "1") (pinfunction "1_1") (pintype "passive"))
      (node (ref "C70") (pin "1") (pinfunction "1_1") (pintype "passive"))
      (node (ref "C78") (pin "1") (pinfunction "1_1") (pintype "passive"))
      (node (ref "C79") (pin "1") (pinfunction "1_1") (pintype "passive"))
      (node (ref "C80") (pin "1") (pinfunction "1_1") (pintype "passive"))
      (node (ref "C87") (pin "1") (pinfunction "1_1") (pintype "passive"))
      (node (ref "C88") (pin "1") (pinfunction "1_1") (pintype "passive"))
      (node (ref "C89") (pin "1") (pinfunction "1_1") (pintype "passive"))
      (node (ref "SENSOR") (pin "A10") (pinfunction "VDD18_A10") (pintype "power_in"))
      (node (ref "SENSOR") (pin "A15") (pinfunction "VDD18_A15") (pintype "power_in"))
      (node (ref "SENSOR") (pin "A16") (pinfunction "VDD18_A16") (pintype "power_in"))
      (node (ref "SENSOR") (pin "A22") (pinfunction "VDD18_A22") (pintype "power_in"))
      (node (ref "SENSOR") (pin "A26") (pinfunction "VDD18_A26") (pintype "power_in"))
      (node (ref "SENSOR") (pin "A27") (pinfunction "VDD18_A27") (pintype "power_in"))
      (node (ref "SENSOR") (pin "B4") (pinfunction "VDD18_B4") (pintype "power_in"))
      (node (ref "SENSOR") (pin "E1") (pinfunction "VDD18_PLL_E1") (pintype "power_in"))
      (node (ref "SENSOR") (pin "H10") (pinfunction "VDD18_H10") (pintype "power_in"))
      (node (ref "SENSOR") (pin "H15") (pinfunction "VDD18_H15") (pintype "power_in"))
      (node (ref "SENSOR") (pin "H16") (pinfunction "VDD18_H16") (pintype "power_in"))
      (node (ref "SENSOR") (pin "H22") (pinfunction "VDD18_H22") (pintype "power_in"))
      (node (ref "SENSOR") (pin "H26") (pinfunction "VDD18_H26") (pintype "power_in"))
      (node (ref "SENSOR") (pin "H5") (pinfunction "VDD18_H5") (pintype "power_in"))
      (node (ref "TP5") (pin "TP") (pinfunction "TP_TP") (pintype "input"))
      (node (ref "U5") (pin "14") (pinfunction "VCCA_14") (pintype "power_in"))
      (node (ref "U5") (pin "15") (pinfunction "DIR1_15") (pintype "input"))
      (node (ref "U5") (pin "16") (pinfunction "DIR2_16") (pintype "input"))
      (node (ref "U5") (pin "5") (pinfunction "DIR3_5") (pintype "input"))
      (node (ref "U6") (pin "14") (pinfunction "VCCA_14") (pintype "power_in"))
      (node (ref "U6") (pin "15") (pinfunction "DIR1_15") (pintype "input"))
      (node (ref "U6") (pin "5") (pinfunction "DIR3_5") (pintype "input"))
      (node (ref "U6") (pin "6") (pinfunction "DIR4_6") (pintype "input"))
      (node (ref "X-NORTH") (pin "49") (pinfunction "49_49") (pintype "bidirectional"))
      (node (ref "X-NORTH") (pin "55") (pinfunction "55_55") (pintype "bidirectional"))
      (node (ref "X-NORTH") (pin "61") (pinfunction "61_61") (pintype "bidirectional"))
      (node (ref "X-NORTH") (pin "67") (pinfunction "67_67") (pintype "bidirectional"))
      (node (ref "X-NORTH") (pin "73") (pinfunction "73_73") (pintype "bidirectional"))
      (node (ref "X-NORTH") (pin "79") (pinfunction "79_79") (pintype "bidirectional"))
      (node (ref "X-NORTH") (pin "85") (pinfunction "85_85") (pintype "bidirectional"))
      (node (ref "X-NORTH") (pin "91") (pinfunction "91_91") (pintype "bidirectional"))
      (node (ref "X-NORTH") (pin "97") (pinfunction "97_97") (pintype "bidirectional"))
    )
    (net (code "102") (name "N_VN_CV") (class "Default")
      (node (ref "C9") (pin "1") (pinfunction "1_1") (pintype "passive"))
      (node (ref "R4") (pin "1") (pinfunction "1_1") (pintype "passive"))
      (node (ref "X-NORTH") (pin "4") (pinfunction "4_4") (pintype "bidirectional"))
    )
    (net (code "103") (name "N_VN_OV") (class "Default")
      (node (ref "UNN") (pin "7") (pinfunction "OUTB_7") (pintype "output"))
      (node (ref "X-NORTH") (pin "3") (pinfunction "3_3") (pintype "bidirectional"))
    )
    (net (code "104") (name "N_VN_UV") (class "Default")
      (node (ref "UNN") (pin "1") (pinfunction "OUTA_1") (pintype "output"))
      (node (ref "X-NORTH") (pin "9") (pinfunction "9_9") (pintype "bidirectional"))
    )
    (net (code "105") (name "N_VW") (class "Default")
      (node (ref "C57") (pin "1") (pinfunction "1_1") (pintype "passive"))
      (node (ref "C58") (pin "1") (pinfunction "1_1") (pintype "passive"))
      (node (ref "C92") (pin "1") (pinfunction "1_1") (pintype "passive"))
      (node (ref "SENSOR") (pin "E2") (pinfunction "VDD_RES_E2") (pintype "power_in"))
      (node (ref "SENSOR") (pin "G4") (pinfunction "VDD_RES_G4") (pintype "power_in"))
      (node (ref "TP8") (pin "TP") (pinfunction "TP_TP") (pintype "input"))
      (node (ref "X-NORTH") (pin "13") (pinfunction "13_13") (pintype "bidirectional"))
      (node (ref "X-NORTH") (pin "19") (pinfunction "19_19") (pintype "bidirectional"))
      (node (ref "X-NORTH") (pin "25") (pinfunction "25_25") (pintype "bidirectional"))
      (node (ref "X-NORTH") (pin "31") (pinfunction "31_31") (pintype "bidirectional"))
      (node (ref "X-NORTH") (pin "37") (pinfunction "37_37") (pintype "bidirectional"))
    )
    (net (code "106") (name "N_VW_CV") (class "Default")
      (node (ref "C8") (pin "1") (pinfunction "1_1") (pintype "passive"))
      (node (ref "R1") (pin "1") (pinfunction "1_1") (pintype "passive"))
      (node (ref "X-NORTH") (pin "2") (pinfunction "2_2") (pintype "bidirectional"))
    )
    (net (code "107") (name "N_VW_OV") (class "Default")
      (node (ref "UNW") (pin "7") (pinfunction "OUTB_7") (pintype "output"))
      (node (ref "X-NORTH") (pin "1") (pinfunction "1_1") (pintype "bidirectional"))
    )
    (net (code "108") (name "N_VW_UV") (class "Default")
      (node (ref "UNW") (pin "1") (pinfunction "OUTA_1") (pintype "output"))
      (node (ref "X-NORTH") (pin "7") (pinfunction "7_7") (pintype "bidirectional"))
    )
    (net (code "109") (name "Net-(SENSORB-CMDN)") (class "Default")
      (node (ref "C61") (pin "1") (pinfunction "1_1") (pintype "passive"))
      (node (ref "SENSOR") (pin "F1") (pinfunction "CMDN_F1") (pintype "bidirectional"))
    )
    (net (code "110") (name "Net-(SENSORB-CMDP)") (class "Default")
      (node (ref "C22") (pin "2") (pinfunction "2_2") (pintype "passive"))
      (node (ref "SENSOR") (pin "F2") (pinfunction "CMDP_F2") (pintype "bidirectional"))
    )
    (net (code "111") (name "Net-(SENSORB-CMDP_COMP)") (class "Default")
      (node (ref "C28") (pin "2") (pinfunction "2_2") (pintype "passive"))
      (node (ref "SENSOR") (pin "H3") (pinfunction "CMDP_COMP_H3") (pintype "bidirectional"))
    )
    (net (code "112") (name "Net-(SENSORB-CMDP_COMP_INV)") (class "Default")
      (node (ref "C27") (pin "2") (pinfunction "2_2") (pintype "passive"))
      (node (ref "SENSOR") (pin "F3") (pinfunction "CMDP_COMP_INV_F3") (pintype "bidirectional"))
    )
    (net (code "113") (name "Net-(SENSORB-CMD_COLAMP)") (class "Default")
      (node (ref "C25") (pin "2") (pinfunction "2_2") (pintype "passive"))
      (node (ref "SENSOR") (pin "C6") (pinfunction "CMD_COLAMP_C6") (pintype "bidirectional"))
    )
    (net (code "114") (name "Net-(SENSORB-CMD_COL_LOAD)") (class "Default")
      (node (ref "C23") (pin "2") (pinfunction "2_2") (pintype "passive"))
      (node (ref "SENSOR") (pin "B1") (pinfunction "CMD_COL_LOAD_B1") (pintype "bidirectional"))
    )
    (net (code "115") (name "Net-(SENSORB-CMD_COL_PC)") (class "Default")
      (node (ref "C26") (pin "2") (pinfunction "2_2") (pintype "passive"))
      (node (ref "SENSOR") (pin "D1") (pinfunction "CMD_COL_PC_D1") (pintype "bidirectional"))
    )
    (net (code "116") (name "Net-(SENSORB-CMD_LVDS)") (class "Default")
      (node (ref "C62") (pin "1") (pinfunction "1_1") (pintype "passive"))
      (node (ref "SENSOR") (pin "C1") (pinfunction "CMD_LVDS_C1") (pintype "bidirectional"))
    )
    (net (code "117") (name "Net-(SENSORB-CMD_RAMP)") (class "Default")
      (node (ref "C24") (pin "2") (pinfunction "2_2") (pintype "passive"))
      (node (ref "SENSOR") (pin "B29") (pinfunction "CMD_RAMP_B29") (pintype "bidirectional"))
    )
    (net (code "118") (name "Net-(SENSORB-VBGAP)") (class "Default")
      (node (ref "C64") (pin "1") (pinfunction "1_1") (pintype "passive"))
      (node (ref "SENSOR") (pin "C29") (pinfunction "VBGAP_C29") (pintype "bidirectional"))
    )
    (net (code "119") (name "Net-(SENSORB-VCLAMP)") (class "Default")
      (node (ref "C63") (pin "1") (pinfunction "1_1") (pintype "passive"))
      (node (ref "SENSOR") (pin "D4") (pinfunction "VCLAMP_D4") (pintype "bidirectional"))
    )
    (net (code "120") (name "Net-(SENSORB-VCLAMP_ADC)") (class "Default")
      (node (ref "C60") (pin "1") (pinfunction "1_1") (pintype "passive"))
      (node (ref "SENSOR") (pin "G2") (pinfunction "VCLAMP_ADC_G2") (pintype "bidirectional"))
    )
    (net (code "121") (name "Net-(SENSORB-VPCH_H)") (class "Default")
      (node (ref "C71") (pin "1") (pinfunction "1_1") (pintype "passive"))
      (node (ref "SENSOR") (pin "C4") (pinfunction "VPCH_H_C4") (pintype "bidirectional"))
    )
    (net (code "122") (name "Net-(SENSORB-VPCH_L)") (class "Default")
      (node (ref "C14") (pin "1") (pinfunction "1_1") (pintype "passive"))
      (node (ref "SENSOR") (pin "A4") (pinfunction "VPCH_L_A4") (pintype "bidirectional"))
    )
    (net (code "123") (name "Net-(SENSORB-VREF)") (class "Default")
      (node (ref "C29") (pin "1") (pinfunction "1_1") (pintype "passive"))
      (node (ref "SENSOR") (pin "A3") (pinfunction "VREF_A3") (pintype "bidirectional"))
    )
    (net (code "124") (name "Net-(SENSORB-VREF_ADC)") (class "Default")
      (node (ref "C30") (pin "1") (pinfunction "1_1") (pintype "passive"))
      (node (ref "SENSOR") (pin "B3") (pinfunction "VREF_ADC_B3") (pintype "bidirectional"))
    )
    (net (code "125") (name "Net-(SENSORB-VRES_L)") (class "Default")
      (node (ref "C15") (pin "1") (pinfunction "1_1") (pintype "passive"))
      (node (ref "SENSOR") (pin "D5") (pinfunction "VRES_L_D5") (pintype "bidirectional"))
    )
    (net (code "126") (name "Net-(SENSORB-VTF_LOW0)") (class "Default")
      (node (ref "C18") (pin "1") (pinfunction "1_1") (pintype "passive"))
      (node (ref "SENSOR") (pin "C5") (pinfunction "VTF_LOW0_C5") (pintype "bidirectional"))
    )
    (net (code "127") (name "Net-(SENSORB-VTF_LOW1)") (class "Default")
      (node (ref "C19") (pin "1") (pinfunction "1_1") (pintype "passive"))
      (node (ref "SENSOR") (pin "D6") (pinfunction "VTF_LOW1_D6") (pintype "bidirectional"))
    )
    (net (code "128") (name "Net-(SENSORB-VTF_LOW2)") (class "Default")
      (node (ref "C20") (pin "1") (pinfunction "1_1") (pintype "passive"))
      (node (ref "SENSOR") (pin "B30") (pinfunction "VTF_LOW2_B30") (pintype "bidirectional"))
    )
    (net (code "129") (name "Net-(SENSORB-VTF_LOW3)") (class "Default")
      (node (ref "C21") (pin "1") (pinfunction "1_1") (pintype "passive"))
      (node (ref "SENSOR") (pin "C30") (pinfunction "VTF_LOW3_C30") (pintype "bidirectional"))
    )
    (net (code "130") (name "Net-(U3-ADJ)") (class "Default")
      (node (ref "R21") (pin "1") (pinfunction "1_1") (pintype "passive"))
      (node (ref "R22") (pin "2") (pinfunction "2_2") (pintype "passive"))
      (node (ref "U3") (pin "5") (pinfunction "ADJ_5") (pintype "input"))
    )
    (net (code "131") (name "Net-(U6-B4)") (class "Default")
      (node (ref "TP9") (pin "TP") (pinfunction "TP_TP") (pintype "input"))
      (node (ref "U6") (pin "9") (pinfunction "B4_9") (pintype "bidirectional"))
    )
    (net (code "132") (name "Net-(UEP-WP)") (class "Default")
      (node (ref "R1X") (pin "2") (pinfunction "2_2") (pintype "passive"))
      (node (ref "R2X") (pin "1") (pinfunction "1_1") (pintype "passive"))
      (node (ref "UEP") (pin "7") (pinfunction "WP_7") (pintype "input"))
    )
    (net (code "133") (name "Net-(UNE-VINA+)") (class "Default")
      (node (ref "R7") (pin "2") (pinfunction "2_2") (pintype "passive"))
      (node (ref "R8") (pin "1") (pinfunction "1_1") (pintype "passive"))
      (node (ref "UNE") (pin "3") (pinfunction "VINA+_3") (pintype "input"))
    )
    (net (code "134") (name "Net-(UNE-VINB-)") (class "Default")
      (node (ref "R8") (pin "2") (pinfunction "2_2") (pintype "passive"))
      (node (ref "R9") (pin "1") (pinfunction "1_1") (pintype "passive"))
      (node (ref "UNE") (pin "6") (pinfunction "VINB-_6") (pintype "input"))
    )
    (net (code "135") (name "Net-(UNN-VINA+)") (class "Default")
      (node (ref "R4") (pin "2") (pinfunction "2_2") (pintype "passive"))
      (node (ref "R5") (pin "1") (pinfunction "1_1") (pintype "passive"))
      (node (ref "UNN") (pin "3") (pinfunction "VINA+_3") (pintype "input"))
    )
    (net (code "136") (name "Net-(UNN-VINB-)") (class "Default")
      (node (ref "R5") (pin "2") (pinfunction "2_2") (pintype "passive"))
      (node (ref "R6") (pin "1") (pinfunction "1_1") (pintype "passive"))
      (node (ref "UNN") (pin "6") (pinfunction "VINB-_6") (pintype "input"))
    )
    (net (code "137") (name "Net-(UNW-VINA+)") (class "Default")
      (node (ref "R1") (pin "2") (pinfunction "2_2") (pintype "passive"))
      (node (ref "R2") (pin "1") (pinfunction "1_1") (pintype "passive"))
      (node (ref "UNW") (pin "3") (pinfunction "VINA+_3") (pintype "input"))
    )
    (net (code "138") (name "Net-(UNW-VINB-)") (class "Default")
      (node (ref "R2") (pin "2") (pinfunction "2_2") (pintype "passive"))
      (node (ref "R3") (pin "1") (pinfunction "1_1") (pintype "passive"))
      (node (ref "UNW") (pin "6") (pinfunction "VINB-_6") (pintype "input"))
    )
    (net (code "139") (name "Net-(USE-VINA+)") (class "Default")
      (node (ref "R10") (pin "2") (pinfunction "2_2") (pintype "passive"))
      (node (ref "R11") (pin "1") (pinfunction "1_1") (pintype "passive"))
      (node (ref "USE") (pin "3") (pinfunction "VINA+_3") (pintype "input"))
    )
    (net (code "140") (name "Net-(USE-VINB-)") (class "Default")
      (node (ref "R11") (pin "2") (pinfunction "2_2") (pintype "passive"))
      (node (ref "R12") (pin "1") (pinfunction "1_1") (pintype "passive"))
      (node (ref "USE") (pin "6") (pinfunction "VINB-_6") (pintype "input"))
    )
    (net (code "141") (name "Net-(USS-VINA+)") (class "Default")
      (node (ref "R13") (pin "2") (pinfunction "2_2") (pintype "passive"))
      (node (ref "R14") (pin "1") (pinfunction "1_1") (pintype "passive"))
      (node (ref "USS") (pin "3") (pinfunction "VINA+_3") (pintype "input"))
    )
    (net (code "142") (name "Net-(USS-VINB-)") (class "Default")
      (node (ref "R14") (pin "2") (pinfunction "2_2") (pintype "passive"))
      (node (ref "R15") (pin "1") (pinfunction "1_1") (pintype "passive"))
      (node (ref "USS") (pin "6") (pinfunction "VINB-_6") (pintype "input"))
    )
    (net (code "143") (name "Net-(USW-VINA+)") (class "Default")
      (node (ref "R16") (pin "2") (pinfunction "2_2") (pintype "passive"))
      (node (ref "R17") (pin "1") (pinfunction "1_1") (pintype "passive"))
      (node (ref "USW") (pin "3") (pinfunction "VINA+_3") (pintype "input"))
    )
    (net (code "144") (name "Net-(USW-VINB-)") (class "Default")
      (node (ref "R17") (pin "2") (pinfunction "2_2") (pintype "passive"))
      (node (ref "R18") (pin "1") (pinfunction "1_1") (pintype "passive"))
      (node (ref "USW") (pin "6") (pinfunction "VINB-_6") (pintype "input"))
    )
    (net (code "145") (name "S00_N") (class "Default")
      (node (ref "X-SOUTH") (pin "16") (pinfunction "16_16") (pintype "bidirectional"))
    )
    (net (code "146") (name "S00_P") (class "Default")
      (node (ref "X-SOUTH") (pin "14") (pinfunction "14_14") (pintype "bidirectional"))
    )
    (net (code "147") (name "S01_N") (class "Default")
      (node (ref "X-SOUTH") (pin "17") (pinfunction "17_17") (pintype "bidirectional"))
    )
    (net (code "148") (name "S01_P") (class "Default")
      (node (ref "X-SOUTH") (pin "15") (pinfunction "15_15") (pintype "bidirectional"))
    )
    (net (code "149") (name "S02_N") (class "Default")
      (node (ref "X-SOUTH") (pin "22") (pinfunction "22_22") (pintype "bidirectional"))
    )
    (net (code "150") (name "S02_P") (class "Default")
      (node (ref "X-SOUTH") (pin "20") (pinfunction "20_20") (pintype "bidirectional"))
    )
    (net (code "151") (name "S03_N") (class "Default")
      (node (ref "X-SOUTH") (pin "23") (pinfunction "23_23") (pintype "bidirectional"))
    )
    (net (code "152") (name "S03_P") (class "Default")
      (node (ref "X-SOUTH") (pin "21") (pinfunction "21_21") (pintype "bidirectional"))
    )
    (net (code "153") (name "S04_N") (class "Default")
      (node (ref "SENSOR") (pin "C24") (pinfunction "OUT32_N_C24") (pintype "output"))
      (node (ref "X-SOUTH") (pin "28") (pinfunction "28_28") (pintype "bidirectional"))
    )
    (net (code "154") (name "S04_P") (class "Default")
      (node (ref "SENSOR") (pin "C25") (pinfunction "OUT32_P_C25") (pintype "output"))
      (node (ref "X-SOUTH") (pin "26") (pinfunction "26_26") (pintype "bidirectional"))
    )
    (net (code "155") (name "S05_N") (class "Default")
      (node (ref "X-SOUTH") (pin "29") (pinfunction "29_29") (pintype "bidirectional"))
    )
    (net (code "156") (name "S05_P") (class "Default")
      (node (ref "X-SOUTH") (pin "27") (pinfunction "27_27") (pintype "bidirectional"))
    )
    (net (code "157") (name "S06_N") (class "Default")
      (node (ref "SENSOR") (pin "D23") (pinfunction "OUT30_N_D23") (pintype "output"))
      (node (ref "X-SOUTH") (pin "34") (pinfunction "34_34") (pintype "bidirectional"))
    )
    (net (code "158") (name "S06_P") (class "Default")
      (node (ref "SENSOR") (pin "D24") (pinfunction "OUT30_P_D24") (pintype "output"))
      (node (ref "X-SOUTH") (pin "32") (pinfunction "32_32") (pintype "bidirectional"))
    )
    (net (code "159") (name "S07_N") (class "Default")
      (node (ref "SENSOR") (pin "B24") (pinfunction "OUT31_N_B24") (pintype "output"))
      (node (ref "X-SOUTH") (pin "35") (pinfunction "35_35") (pintype "bidirectional"))
    )
    (net (code "160") (name "S07_P") (class "Default")
      (node (ref "SENSOR") (pin "B25") (pinfunction "OUT31_P_B25") (pintype "output"))
      (node (ref "X-SOUTH") (pin "33") (pinfunction "33_33") (pintype "bidirectional"))
    )
    (net (code "161") (name "S08_N") (class "Default")
      (node (ref "SENSOR") (pin "D21") (pinfunction "OUT27_N_D21") (pintype "output"))
      (node (ref "X-SOUTH") (pin "40") (pinfunction "40_40") (pintype "bidirectional"))
    )
    (net (code "162") (name "S08_P") (class "Default")
      (node (ref "SENSOR") (pin "D22") (pinfunction "OUT27_P_D22") (pintype "output"))
      (node (ref "X-SOUTH") (pin "38") (pinfunction "38_38") (pintype "bidirectional"))
    )
    (net (code "163") (name "S09_N") (class "Default")
      (node (ref "SENSOR") (pin "A23") (pinfunction "OUT29_N_A23") (pintype "output"))
      (node (ref "X-SOUTH") (pin "41") (pinfunction "41_41") (pintype "bidirectional"))
    )
    (net (code "164") (name "S09_P") (class "Default")
      (node (ref "SENSOR") (pin "A24") (pinfunction "OUT29_P_A24") (pintype "output"))
      (node (ref "X-SOUTH") (pin "39") (pinfunction "39_39") (pintype "bidirectional"))
    )
    (net (code "165") (name "S10_N") (class "Default")
      (node (ref "SENSOR") (pin "C21") (pinfunction "OUT28_N_C21") (pintype "output"))
      (node (ref "X-SOUTH") (pin "46") (pinfunction "46_46") (pintype "bidirectional"))
    )
    (net (code "166") (name "S10_P") (class "Default")
      (node (ref "SENSOR") (pin "C22") (pinfunction "OUT28_P_C22") (pintype "output"))
      (node (ref "X-SOUTH") (pin "44") (pinfunction "44_44") (pintype "bidirectional"))
    )
    (net (code "167") (name "S11_N") (class "Default")
      (node (ref "SENSOR") (pin "B20") (pinfunction "OUT26_N_B20") (pintype "output"))
      (node (ref "X-SOUTH") (pin "47") (pinfunction "47_47") (pintype "bidirectional"))
    )
    (net (code "168") (name "S11_P") (class "Default")
      (node (ref "SENSOR") (pin "B21") (pinfunction "OUT26_P_B21") (pintype "output"))
      (node (ref "X-SOUTH") (pin "45") (pinfunction "45_45") (pintype "bidirectional"))
    )
    (net (code "169") (name "S12_N") (class "Default")
      (node (ref "SENSOR") (pin "D19") (pinfunction "OUT24_N_D19") (pintype "output"))
      (node (ref "X-SOUTH") (pin "52") (pinfunction "52_52") (pintype "bidirectional"))
    )
    (net (code "170") (name "S12_P") (class "Default")
      (node (ref "SENSOR") (pin "D20") (pinfunction "OUT24_P_D20") (pintype "output"))
      (node (ref "X-SOUTH") (pin "50") (pinfunction "50_50") (pintype "bidirectional"))
    )
    (net (code "171") (name "S13_N") (class "Default")
      (node (ref "SENSOR") (pin "A19") (pinfunction "OUT23_N_A19") (pintype "output"))
      (node (ref "X-SOUTH") (pin "53") (pinfunction "53_53") (pintype "bidirectional"))
    )
    (net (code "172") (name "S13_P") (class "Default")
      (node (ref "SENSOR") (pin "A20") (pinfunction "OUT23_P_A20") (pintype "output"))
      (node (ref "X-SOUTH") (pin "51") (pinfunction "51_51") (pintype "bidirectional"))
    )
    (net (code "173") (name "S14_N") (class "Default")
      (node (ref "SENSOR") (pin "C19") (pinfunction "OUT25_N_C19") (pintype "output"))
      (node (ref "X-SOUTH") (pin "58") (pinfunction "58_58") (pintype "bidirectional"))
    )
    (net (code "174") (name "S14_P") (class "Default")
      (node (ref "SENSOR") (pin "C20") (pinfunction "OUT25_P_C20") (pintype "output"))
      (node (ref "X-SOUTH") (pin "56") (pinfunction "56_56") (pintype "bidirectional"))
    )
    (net (code "175") (name "S15_N") (class "Default")
      (node (ref "SENSOR") (pin "B18") (pinfunction "OUT22_N_B18") (pintype "output"))
      (node (ref "X-SOUTH") (pin "59") (pinfunction "59_59") (pintype "bidirectional"))
    )
    (net (code "176") (name "S15_P") (class "Default")
      (node (ref "SENSOR") (pin "B19") (pinfunction "OUT22_P_B19") (pintype "output"))
      (node (ref "X-SOUTH") (pin "57") (pinfunction "57_57") (pintype "bidirectional"))
    )
    (net (code "177") (name "S16_N") (class "Default")
      (node (ref "SENSOR") (pin "C17") (pinfunction "OUT21_N_C17") (pintype "output"))
      (node (ref "X-SOUTH") (pin "64") (pinfunction "64_64") (pintype "bidirectional"))
    )
    (net (code "178") (name "S16_P") (class "Default")
      (node (ref "SENSOR") (pin "C18") (pinfunction "OUT21_P_C18") (pintype "output"))
      (node (ref "X-SOUTH") (pin "62") (pinfunction "62_62") (pintype "bidirectional"))
    )
    (net (code "179") (name "S17_N") (class "Default")
      (node (ref "SENSOR") (pin "A17") (pinfunction "OUT19_N_A17") (pintype "output"))
      (node (ref "X-SOUTH") (pin "65") (pinfunction "65_65") (pintype "bidirectional"))
    )
    (net (code "180") (name "S17_P") (class "Default")
      (node (ref "SENSOR") (pin "A18") (pinfunction "OUT19_P_A18") (pintype "output"))
      (node (ref "X-SOUTH") (pin "63") (pinfunction "63_63") (pintype "bidirectional"))
    )
    (net (code "181") (name "S18_N") (class "Default")
      (node (ref "SENSOR") (pin "D17") (pinfunction "OUT20_N_D17") (pintype "output"))
      (node (ref "X-SOUTH") (pin "70") (pinfunction "70_70") (pintype "bidirectional"))
    )
    (net (code "182") (name "S18_P") (class "Default")
      (node (ref "SENSOR") (pin "D18") (pinfunction "OUT20_P_D18") (pintype "output"))
      (node (ref "X-SOUTH") (pin "68") (pinfunction "68_68") (pintype "bidirectional"))
    )
    (net (code "183") (name "S19_N") (class "Default")
      (node (ref "SENSOR") (pin "B16") (pinfunction "OUT18_N_B16") (pintype "output"))
      (node (ref "X-SOUTH") (pin "71") (pinfunction "71_71") (pintype "bidirectional"))
    )
    (net (code "184") (name "S19_P") (class "Default")
      (node (ref "SENSOR") (pin "B17") (pinfunction "OUT18_P_B17") (pintype "output"))
      (node (ref "X-SOUTH") (pin "69") (pinfunction "69_69") (pintype "bidirectional"))
    )
    (net (code "185") (name "S20_N") (class "Default")
      (node (ref "SENSOR") (pin "D15") (pinfunction "OUT17_N_D15") (pintype "output"))
      (node (ref "X-SOUTH") (pin "76") (pinfunction "76_76") (pintype "bidirectional"))
    )
    (net (code "186") (name "S20_P") (class "Default")
      (node (ref "SENSOR") (pin "D16") (pinfunction "OUT17_P_D16") (pintype "output"))
      (node (ref "X-SOUTH") (pin "74") (pinfunction "74_74") (pintype "bidirectional"))
    )
    (net (code "187") (name "S21_N") (class "Default")
      (node (ref "SENSOR") (pin "B14") (pinfunction "OUT16_N_B14") (pintype "output"))
      (node (ref "X-SOUTH") (pin "77") (pinfunction "77_77") (pintype "bidirectional"))
    )
    (net (code "188") (name "S21_P") (class "Default")
      (node (ref "SENSOR") (pin "B15") (pinfunction "OUT16_P_B15") (pintype "output"))
      (node (ref "X-SOUTH") (pin "75") (pinfunction "75_75") (pintype "bidirectional"))
    )
    (net (code "189") (name "S22_N") (class "Default")
      (node (ref "SENSOR") (pin "D13") (pinfunction "OUT15_N_D13") (pintype "output"))
      (node (ref "X-SOUTH") (pin "82") (pinfunction "82_82") (pintype "bidirectional"))
    )
    (net (code "190") (name "S22_P") (class "Default")
      (node (ref "SENSOR") (pin "D14") (pinfunction "OUT15_P_D14") (pintype "output"))
      (node (ref "X-SOUTH") (pin "80") (pinfunction "80_80") (pintype "bidirectional"))
    )
    (net (code "191") (name "S23_N") (class "Default")
      (node (ref "SENSOR") (pin "A13") (pinfunction "OUT13_N_A13") (pintype "output"))
      (node (ref "X-SOUTH") (pin "83") (pinfunction "83_83") (pintype "bidirectional"))
    )
    (net (code "192") (name "S23_P") (class "Default")
      (node (ref "SENSOR") (pin "A14") (pinfunction "OUT13_P_A14") (pintype "output"))
      (node (ref "X-SOUTH") (pin "81") (pinfunction "81_81") (pintype "bidirectional"))
    )
    (net (code "193") (name "S24_N") (class "Default")
      (node (ref "SENSOR") (pin "C13") (pinfunction "OUT14_N_C13") (pintype "output"))
      (node (ref "X-SOUTH") (pin "88") (pinfunction "88_88") (pintype "bidirectional"))
    )
    (net (code "194") (name "S24_P") (class "Default")
      (node (ref "SENSOR") (pin "C14") (pinfunction "OUT14_P_C14") (pintype "output"))
      (node (ref "X-SOUTH") (pin "86") (pinfunction "86_86") (pintype "bidirectional"))
    )
    (net (code "195") (name "S25_N") (class "Default")
      (node (ref "SENSOR") (pin "B12") (pinfunction "OUT12_N_B12") (pintype "output"))
      (node (ref "X-SOUTH") (pin "89") (pinfunction "89_89") (pintype "bidirectional"))
    )
    (net (code "196") (name "S25_P") (class "Default")
      (node (ref "SENSOR") (pin "B13") (pinfunction "OUT12_P_B13") (pintype "output"))
      (node (ref "X-SOUTH") (pin "87") (pinfunction "87_87") (pintype "bidirectional"))
    )
    (net (code "197") (name "S26_N") (class "Default")
      (node (ref "SENSOR") (pin "D11") (pinfunction "OUT10_N_D11") (pintype "output"))
      (node (ref "X-SOUTH") (pin "94") (pinfunction "94_94") (pintype "bidirectional"))
    )
    (net (code "198") (name "S26_P") (class "Default")
      (node (ref "SENSOR") (pin "D12") (pinfunction "OUT10_P_D12") (pintype "output"))
      (node (ref "X-SOUTH") (pin "92") (pinfunction "92_92") (pintype "bidirectional"))
    )
    (net (code "199") (name "S27_N") (class "Default")
      (node (ref "SENSOR") (pin "A11") (pinfunction "OUT9_N_A11") (pintype "output"))
      (node (ref "X-SOUTH") (pin "95") (pinfunction "95_95") (pintype "bidirectional"))
    )
    (net (code "200") (name "S27_P") (class "Default")
      (node (ref "SENSOR") (pin "A12") (pinfunction "OUT9_P_A12") (pintype "output"))
      (node (ref "X-SOUTH") (pin "93") (pinfunction "93_93") (pintype "bidirectional"))
    )
    (net (code "201") (name "S28_N") (class "Default")
      (node (ref "SENSOR") (pin "C11") (pinfunction "OUT11_N_C11") (pintype "output"))
      (node (ref "X-SOUTH") (pin "100") (pinfunction "100_100") (pintype "bidirectional"))
    )
    (net (code "202") (name "S28_P") (class "Default")
      (node (ref "SENSOR") (pin "C12") (pinfunction "OUT11_P_C12") (pintype "output"))
      (node (ref "X-SOUTH") (pin "98") (pinfunction "98_98") (pintype "bidirectional"))
    )
    (net (code "203") (name "S29_N") (class "Default")
      (node (ref "SENSOR") (pin "B10") (pinfunction "OUT8_N_B10") (pintype "output"))
      (node (ref "X-SOUTH") (pin "101") (pinfunction "101_101") (pintype "bidirectional"))
    )
    (net (code "204") (name "S29_P") (class "Default")
      (node (ref "SENSOR") (pin "B11") (pinfunction "OUT8_P_B11") (pintype "output"))
      (node (ref "X-SOUTH") (pin "99") (pinfunction "99_99") (pintype "bidirectional"))
    )
    (net (code "205") (name "S30_N") (class "Default")
      (node (ref "SENSOR") (pin "C9") (pinfunction "OUT7_N_C9") (pintype "output"))
      (node (ref "X-SOUTH") (pin "106") (pinfunction "106_106") (pintype "bidirectional"))
    )
    (net (code "206") (name "S30_P") (class "Default")
      (node (ref "SENSOR") (pin "C10") (pinfunction "OUT7_P_C10") (pintype "output"))
      (node (ref "X-SOUTH") (pin "104") (pinfunction "104_104") (pintype "bidirectional"))
    )
    (net (code "207") (name "S31_N") (class "Default")
      (node (ref "SENSOR") (pin "B8") (pinfunction "OUT5_N_B8") (pintype "output"))
      (node (ref "X-SOUTH") (pin "107") (pinfunction "107_107") (pintype "bidirectional"))
    )
    (net (code "208") (name "S31_P") (class "Default")
      (node (ref "SENSOR") (pin "B9") (pinfunction "OUT5_P_B9") (pintype "output"))
      (node (ref "X-SOUTH") (pin "105") (pinfunction "105_105") (pintype "bidirectional"))
    )
    (net (code "209") (name "S32_N") (class "Default")
      (node (ref "SENSOR") (pin "D9") (pinfunction "OUT6_N_D9") (pintype "output"))
      (node (ref "X-SOUTH") (pin "112") (pinfunction "112_112") (pintype "bidirectional"))
    )
    (net (code "210") (name "S32_P") (class "Default")
      (node (ref "SENSOR") (pin "D10") (pinfunction "OUT6_P_D10") (pintype "output"))
      (node (ref "X-SOUTH") (pin "110") (pinfunction "110_110") (pintype "bidirectional"))
    )
    (net (code "211") (name "S33_N") (class "Default")
      (node (ref "SENSOR") (pin "A7") (pinfunction "OUT2_N_A7") (pintype "output"))
      (node (ref "X-SOUTH") (pin "113") (pinfunction "113_113") (pintype "bidirectional"))
    )
    (net (code "212") (name "S33_P") (class "Default")
      (node (ref "SENSOR") (pin "A8") (pinfunction "OUT2_P_A8") (pintype "output"))
      (node (ref "X-SOUTH") (pin "111") (pinfunction "111_111") (pintype "bidirectional"))
    )
    (net (code "213") (name "S34_N") (class "Default")
      (node (ref "SENSOR") (pin "C7") (pinfunction "OUT4_N_C7") (pintype "output"))
      (node (ref "X-SOUTH") (pin "118") (pinfunction "118_118") (pintype "bidirectional"))
    )
    (net (code "214") (name "S34_P") (class "Default")
      (node (ref "SENSOR") (pin "C8") (pinfunction "OUT4_P_C8") (pintype "output"))
      (node (ref "X-SOUTH") (pin "116") (pinfunction "116_116") (pintype "bidirectional"))
    )
    (net (code "215") (name "S35_N") (class "Default")
      (node (ref "SENSOR") (pin "B6") (pinfunction "OUT1_N_B6") (pintype "output"))
      (node (ref "X-SOUTH") (pin "119") (pinfunction "119_119") (pintype "bidirectional"))
    )
    (net (code "216") (name "S35_P") (class "Default")
      (node (ref "SENSOR") (pin "B7") (pinfunction "OUT1_P_B7") (pintype "output"))
      (node (ref "X-SOUTH") (pin "117") (pinfunction "117_117") (pintype "bidirectional"))
    )
    (net (code "217") (name "S36_N") (class "Default")
      (node (ref "SENSOR") (pin "D7") (pinfunction "OUT3_N_D7") (pintype "output"))
      (node (ref "X-SOUTH") (pin "124") (pinfunction "124_124") (pintype "bidirectional"))
    )
    (net (code "218") (name "S36_P") (class "Default")
      (node (ref "SENSOR") (pin "D8") (pinfunction "OUT3_P_D8") (pintype "output"))
      (node (ref "X-SOUTH") (pin "122") (pinfunction "122_122") (pintype "bidirectional"))
    )
    (net (code "219") (name "S37_N") (class "Default")
      (node (ref "SENSOR") (pin "A5") (pinfunction "OUTCTR_N_A5") (pintype "output"))
      (node (ref "X-SOUTH") (pin "125") (pinfunction "125_125") (pintype "bidirectional"))
    )
    (net (code "220") (name "S37_P") (class "Default")
      (node (ref "SENSOR") (pin "A6") (pinfunction "OUTCTR_P_A6") (pintype "output"))
      (node (ref "X-SOUTH") (pin "123") (pinfunction "123_123") (pintype "bidirectional"))
    )
    (net (code "221") (name "S38_N") (class "Default")
      (node (ref "X-SOUTH") (pin "130") (pinfunction "130_130") (pintype "bidirectional"))
    )
    (net (code "222") (name "S38_P") (class "Default")
      (node (ref "X-SOUTH") (pin "128") (pinfunction "128_128") (pintype "bidirectional"))
    )
    (net (code "223") (name "S39_N") (class "Default")
      (node (ref "U3") (pin "6") (pinfunction "EN_6") (pintype "input"))
      (node (ref "X-SOUTH") (pin "131") (pinfunction "131_131") (pintype "bidirectional"))
    )
    (net (code "224") (name "S39_P") (class "Default")
      (node (ref "X-SOUTH") (pin "129") (pinfunction "129_129") (pintype "bidirectional"))
    )
    (net (code "225") (name "SPI_CLK") (class "Default")
      (node (ref "SENSOR") (pin "H29") (pinfunction "SPI_CLK_H29") (pintype "input"))
      (node (ref "U4") (pin "9") (pinfunction "B4_9") (pintype "bidirectional"))
    )
    (net (code "226") (name "SPI_EN") (class "Default")
      (node (ref "SENSOR") (pin "F28") (pinfunction "SPI_EN_F28") (pintype "input"))
      (node (ref "U4") (pin "12") (pinfunction "B1_12") (pintype "bidirectional"))
    )
    (net (code "227") (name "SPI_IN") (class "Default")
      (node (ref "SENSOR") (pin "E28") (pinfunction "SPI_IN_E28") (pintype "input"))
      (node (ref "U4") (pin "10") (pinfunction "B3_10") (pintype "bidirectional"))
    )
    (net (code "228") (name "SPI_OUT") (class "Default")
      (node (ref "SENSOR") (pin "G28") (pinfunction "SPI_OUT_G28") (pintype "output"))
      (node (ref "U4") (pin "11") (pinfunction "B2_11") (pintype "bidirectional"))
    )
    (net (code "229") (name "SYS_RES_N") (class "Default")
      (node (ref "SENSOR") (pin "F30") (pinfunction "SYS_RES_N_F30") (pintype "input"))
      (node (ref "U5") (pin "10") (pinfunction "B3_10") (pintype "bidirectional"))
    )
    (net (code "230") (name "S_CHK_EN") (class "Default")
      (node (ref "X-SOUTH") (pin "8") (pinfunction "8_8") (pintype "bidirectional"))
    )
    (net (code "231") (name "S_CHK_V") (class "Default")
      (node (ref "C5") (pin "1") (pinfunction "1_1") (pintype "passive"))
      (node (ref "C6") (pin "1") (pinfunction "1_1") (pintype "passive"))
      (node (ref "C7") (pin "1") (pinfunction "1_1") (pintype "passive"))
      (node (ref "R20") (pin "1") (pinfunction "1_1") (pintype "passive"))
      (node (ref "TP3") (pin "TP") (pinfunction "TP_TP") (pintype "input"))
      (node (ref "USE") (pin "8") (pinfunction "VDD_8") (pintype "power_in"))
      (node (ref "USS") (pin "8") (pinfunction "VDD_8") (pintype "power_in"))
      (node (ref "USW") (pin "8") (pinfunction "VDD_8") (pintype "power_in"))
      (node (ref "X-SOUTH") (pin "10") (pinfunction "10_10") (pintype "bidirectional"))
    )
    (net (code "232") (name "S_I2C_EN") (class "Default")
      (node (ref "X-SOUTH") (pin "137") (pinfunction "137_137") (pintype "bidirectional"))
    )
    (net (code "233") (name "S_I2C_V") (class "Default")
      (node (ref "U7") (pin "8") (pinfunction "VCC_8") (pintype "power_in"))
      (node (ref "X-SOUTH") (pin "135") (pinfunction "135_135") (pintype "bidirectional"))
    )
    (net (code "234") (name "S_REF") (class "Default")
      (node (ref "R20") (pin "2") (pinfunction "2_2") (pintype "passive"))
      (node (ref "TP4") (pin "TP") (pinfunction "TP_TP") (pintype "input"))
      (node (ref "U2") (pin "1") (pinfunction "CATHODE_1") (pintype "output"))
      (node (ref "U2") (pin "3") (pinfunction "REF_3") (pintype "input"))
      (node (ref "USE") (pin "2") (pinfunction "VINA-_2") (pintype "input"))
      (node (ref "USE") (pin "5") (pinfunction "VINB+_5") (pintype "input"))
      (node (ref "USS") (pin "2") (pinfunction "VINA-_2") (pintype "input"))
      (node (ref "USS") (pin "5") (pinfunction "VINB+_5") (pintype "input"))
      (node (ref "USW") (pin "2") (pinfunction "VINA-_2") (pintype "input"))
      (node (ref "USW") (pin "5") (pinfunction "VINB+_5") (pintype "input"))
    )
    (net (code "235") (name "S_SCK") (class "Default")
      (node (ref "X-SOUTH") (pin "144") (pinfunction "144_144") (pintype "bidirectional"))
    )
    (net (code "236") (name "S_SCL") (class "Default")
      (node (ref "U7") (pin "2") (pinfunction "SCL_2") (pintype "input"))
      (node (ref "X-SOUTH") (pin "143") (pinfunction "143_143") (pintype "bidirectional"))
    )
    (net (code "237") (name "S_SDA") (class "Default")
      (node (ref "U7") (pin "1") (pinfunction "SDA_1") (pintype "bidirectional"))
      (node (ref "X-SOUTH") (pin "141") (pinfunction "141_141") (pintype "bidirectional"))
    )
    (net (code "238") (name "S_SDI") (class "Default")
      (node (ref "X-SOUTH") (pin "140") (pinfunction "140_140") (pintype "bidirectional"))
    )
    (net (code "239") (name "S_SDO") (class "Default")
      (node (ref "X-SOUTH") (pin "142") (pinfunction "142_142") (pintype "bidirectional"))
    )
    (net (code "240") (name "S_SPI_EN") (class "Default")
      (node (ref "X-SOUTH") (pin "136") (pinfunction "136_136") (pintype "bidirectional"))
    )
    (net (code "241") (name "S_SPI_V") (class "Default")
      (node (ref "X-SOUTH") (pin "134") (pinfunction "134_134") (pintype "bidirectional"))
    )
    (net (code "242") (name "S_VE") (class "Default")
      (node (ref "X-SOUTH") (pin "13") (pinfunction "13_13") (pintype "bidirectional"))
      (node (ref "X-SOUTH") (pin "19") (pinfunction "19_19") (pintype "bidirectional"))
      (node (ref "X-SOUTH") (pin "25") (pinfunction "25_25") (pintype "bidirectional"))
      (node (ref "X-SOUTH") (pin "31") (pinfunction "31_31") (pintype "bidirectional"))
      (node (ref "X-SOUTH") (pin "37") (pinfunction "37_37") (pintype "bidirectional"))
    )
    (net (code "243") (name "S_VE_CV") (class "Default")
      (node (ref "C11") (pin "1") (pinfunction "1_1") (pintype "passive"))
      (node (ref "R10") (pin "1") (pinfunction "1_1") (pintype "passive"))
      (node (ref "X-SOUTH") (pin "2") (pinfunction "2_2") (pintype "bidirectional"))
    )
    (net (code "244") (name "S_VE_OV") (class "Default")
      (node (ref "USE") (pin "7") (pinfunction "OUTB_7") (pintype "output"))
      (node (ref "X-SOUTH") (pin "1") (pinfunction "1_1") (pintype "bidirectional"))
    )
    (net (code "245") (name "S_VE_UV") (class "Default")
      (node (ref "USE") (pin "1") (pinfunction "OUTA_1") (pintype "output"))
      (node (ref "X-SOUTH") (pin "7") (pinfunction "7_7") (pintype "bidirectional"))
    )
    (net (code "246") (name "S_VS") (class "Default")
      (node (ref "C45") (pin "1") (pinfunction "1_1") (pintype "passive"))
      (node (ref "C46") (pin "1") (pinfunction "1_1") (pintype "passive"))
      (node (ref "C47") (pin "1") (pinfunction "1_1") (pintype "passive"))
      (node (ref "C48") (pin "1") (pinfunction "1_1") (pintype "passive"))
      (node (ref "C49") (pin "1") (pinfunction "1_1") (pintype "passive"))
      (node (ref "C72") (pin "1") (pinfunction "1_1") (pintype "passive"))
      (node (ref "C73") (pin "1") (pinfunction "1_1") (pintype "passive"))
      (node (ref "C74") (pin "1") (pinfunction "1_1") (pintype "passive"))
      (node (ref "C81") (pin "1") (pinfunction "1_1") (pintype "passive"))
      (node (ref "C82") (pin "1") (pinfunction "1_1") (pintype "passive"))
      (node (ref "C83") (pin "1") (pinfunction "1_1") (pintype "passive"))
      (node (ref "SENSOR") (pin "A30") (pinfunction "VDD_PIX_A30") (pintype "power_in"))
      (node (ref "SENSOR") (pin "D28") (pinfunction "VDD_PIX_D28") (pintype "power_in"))
      (node (ref "SENSOR") (pin "D30") (pinfunction "VDD_PIX_D30") (pintype "power_in"))
      (node (ref "SENSOR") (pin "G1") (pinfunction "VDD_PIX_G1") (pintype "power_in"))
      (node (ref "SENSOR") (pin "H28") (pinfunction "VDD_PIX_H28") (pintype "power_in"))
      (node (ref "TP6") (pin "TP") (pinfunction "TP_TP") (pintype "input"))
      (node (ref "X-SOUTH") (pin "49") (pinfunction "49_49") (pintype "bidirectional"))
      (node (ref "X-SOUTH") (pin "55") (pinfunction "55_55") (pintype "bidirectional"))
      (node (ref "X-SOUTH") (pin "61") (pinfunction "61_61") (pintype "bidirectional"))
      (node (ref "X-SOUTH") (pin "67") (pinfunction "67_67") (pintype "bidirectional"))
      (node (ref "X-SOUTH") (pin "73") (pinfunction "73_73") (pintype "bidirectional"))
      (node (ref "X-SOUTH") (pin "79") (pinfunction "79_79") (pintype "bidirectional"))
      (node (ref "X-SOUTH") (pin "85") (pinfunction "85_85") (pintype "bidirectional"))
      (node (ref "X-SOUTH") (pin "91") (pinfunction "91_91") (pintype "bidirectional"))
      (node (ref "X-SOUTH") (pin "97") (pinfunction "97_97") (pintype "bidirectional"))
    )
    (net (code "247") (name "S_VS_CV") (class "Default")
      (node (ref "C12") (pin "1") (pinfunction "1_1") (pintype "passive"))
      (node (ref "R13") (pin "1") (pinfunction "1_1") (pintype "passive"))
      (node (ref "X-SOUTH") (pin "4") (pinfunction "4_4") (pintype "bidirectional"))
    )
    (net (code "248") (name "S_VS_OV") (class "Default")
      (node (ref "USS") (pin "7") (pinfunction "OUTB_7") (pintype "output"))
      (node (ref "X-SOUTH") (pin "3") (pinfunction "3_3") (pintype "bidirectional"))
    )
    (net (code "249") (name "S_VS_UV") (class "Default")
      (node (ref "USS") (pin "1") (pinfunction "OUTA_1") (pintype "output"))
      (node (ref "X-SOUTH") (pin "9") (pinfunction "9_9") (pintype "bidirectional"))
    )
    (net (code "250") (name "S_VW") (class "Default")
      (node (ref "C90") (pin "1") (pinfunction "1_1") (pintype "passive"))
      (node (ref "U3") (pin "1") (pinfunction "BIAS_1") (pintype "power_in"))
      (node (ref "U3") (pin "3") (pinfunction "IN_3") (pintype "power_in"))
      (node (ref "X-SOUTH") (pin "109") (pinfunction "109_109") (pintype "bidirectional"))
      (node (ref "X-SOUTH") (pin "115") (pinfunction "115_115") (pintype "bidirectional"))
      (node (ref "X-SOUTH") (pin "121") (pinfunction "121_121") (pintype "bidirectional"))
      (node (ref "X-SOUTH") (pin "127") (pinfunction "127_127") (pintype "bidirectional"))
      (node (ref "X-SOUTH") (pin "133") (pinfunction "133_133") (pintype "bidirectional"))
    )
    (net (code "251") (name "S_VW_CV") (class "Default")
      (node (ref "C13") (pin "1") (pinfunction "1_1") (pintype "passive"))
      (node (ref "R16") (pin "1") (pinfunction "1_1") (pintype "passive"))
      (node (ref "X-SOUTH") (pin "6") (pinfunction "6_6") (pintype "bidirectional"))
    )
    (net (code "252") (name "S_VW_OV") (class "Default")
      (node (ref "USW") (pin "7") (pinfunction "OUTB_7") (pintype "output"))
      (node (ref "X-SOUTH") (pin "5") (pinfunction "5_5") (pintype "bidirectional"))
    )
    (net (code "253") (name "S_VW_UV") (class "Default")
      (node (ref "USW") (pin "1") (pinfunction "OUTA_1") (pintype "output"))
      (node (ref "X-SOUTH") (pin "11") (pinfunction "11_11") (pintype "bidirectional"))
    )
    (net (code "254") (name "TDIG1") (class "Default")
      (node (ref "SENSOR") (pin "G27") (pinfunction "TDIG1_G27") (pintype "output"))
      (node (ref "U5") (pin "9") (pinfunction "B4_9") (pintype "bidirectional"))
    )
    (net (code "255") (name "TDIG2") (class "Default")
      (node (ref "SENSOR") (pin "G26") (pinfunction "TDIG2_G26") (pintype "output"))
      (node (ref "U6") (pin "11") (pinfunction "B2_11") (pintype "bidirectional"))
    )
    (net (code "256") (name "T_EXP1") (class "Default")
      (node (ref "SENSOR") (pin "H30") (pinfunction "T_EXP1_H30") (pintype "input"))
      (node (ref "U5") (pin "12") (pinfunction "B1_12") (pintype "bidirectional"))
    )
    (net (code "257") (name "T_EXP2") (class "Default")
      (node (ref "SENSOR") (pin "E29") (pinfunction "T_EXP2_E29") (pintype "input"))
      (node (ref "U6") (pin "10") (pinfunction "B3_10") (pintype "bidirectional"))
    )
    (net (code "258") (name "VRAMP1") (class "Default")
      (node (ref "C16") (pin "1") (pinfunction "1_1") (pintype "passive"))
      (node (ref "R23") (pin "1") (pinfunction "1_1") (pintype "passive"))
      (node (ref "SENSOR") (pin "G29") (pinfunction "VRAMP1_G29") (pintype "bidirectional"))
    )
    (net (code "259") (name "VRAMP2") (class "Default")
      (node (ref "C17") (pin "1") (pinfunction "1_1") (pintype "passive"))
      (node (ref "R23") (pin "2") (pinfunction "2_2") (pintype "passive"))
      (node (ref "SENSOR") (pin "F29") (pinfunction "VRAMP2_F29") (pintype "bidirectional"))
    )
    (net (code "260") (name "VTREF") (class "Default")
      (node (ref "C65") (pin "1") (pinfunction "1_1") (pintype "passive"))
      (node (ref "C91") (pin "2") (pinfunction "2_2") (pintype "passive"))
      (node (ref "R21") (pin "2") (pinfunction "2_2") (pintype "passive"))
      (node (ref "R24") (pin "1") (pinfunction "1_1") (pintype "passive"))
      (node (ref "SENSOR") (pin "B2") (pinfunction "VTREF_B2") (pintype "bidirectional"))
      (node (ref "U3") (pin "4") (pinfunction "OUT_4") (pintype "power_in"))
    )
    (net (code "261") (name "VTSIG") (class "Default")
      (node (ref "C66") (pin "1") (pinfunction "1_1") (pintype "passive"))
      (node (ref "R24") (pin "2") (pinfunction "2_2") (pintype "passive"))
      (node (ref "SENSOR") (pin "C2") (pinfunction "VTSIG_C2") (pintype "bidirectional"))
    )
    (net (code "262") (name "unconnected-(U1-NC-Pad2)") (class "Default")
      (node (ref "U1") (pin "2") (pinfunction "NC_2") (pintype "no_connect"))
    )
    (net (code "263") (name "unconnected-(U1-NC-Pad4)") (class "Default")
      (node (ref "U1") (pin "4") (pinfunction "NC_4") (pintype "no_connect"))
    )
    (net (code "264") (name "unconnected-(U1-NC-Pad5)") (class "Default")
      (node (ref "U1") (pin "5") (pinfunction "NC_5") (pintype "no_connect"))
    )
    (net (code "265") (name "unconnected-(U2-NC-Pad2)") (class "Default")
      (node (ref "U2") (pin "2") (pinfunction "NC_2") (pintype "no_connect"))
    )
    (net (code "266") (name "unconnected-(U2-NC-Pad4)") (class "Default")
      (node (ref "U2") (pin "4") (pinfunction "NC_4") (pintype "no_connect"))
    )
    (net (code "267") (name "unconnected-(U2-NC-Pad5)") (class "Default")
      (node (ref "U2") (pin "5") (pinfunction "NC_5") (pintype "no_connect"))
    )
    (net (code "268") (name "unconnected-(U7-OS-Pad3)") (class "Default")
      (node (ref "U7") (pin "3") (pinfunction "OS_3") (pintype "output"))
    )
    (net (code "269") (name "unconnected-(X-NORTH-PadM1)") (class "Default")
      (node (ref "X-NORTH") (pin "M1") (pinfunction "M1_M1") (pintype "bidirectional"))
    )
    (net (code "270") (name "unconnected-(X-NORTH-PadM2)") (class "Default")
      (node (ref "X-NORTH") (pin "M2") (pinfunction "M2_M2") (pintype "bidirectional"))
    )
    (net (code "271") (name "unconnected-(X-SOUTH-PadM1)") (class "Default")
      (node (ref "X-SOUTH") (pin "M1") (pinfunction "M1_M1") (pintype "bidirectional"))
    )
    (net (code "272") (name "unconnected-(X-SOUTH-PadM2)") (class "Default")
      (node (ref "X-SOUTH") (pin "M2") (pinfunction "M2_M2") (pintype "bidirectional"))
    )
  )
)
